# watchplb.net
KiCad netlist of a schematic drawn in EAGLE
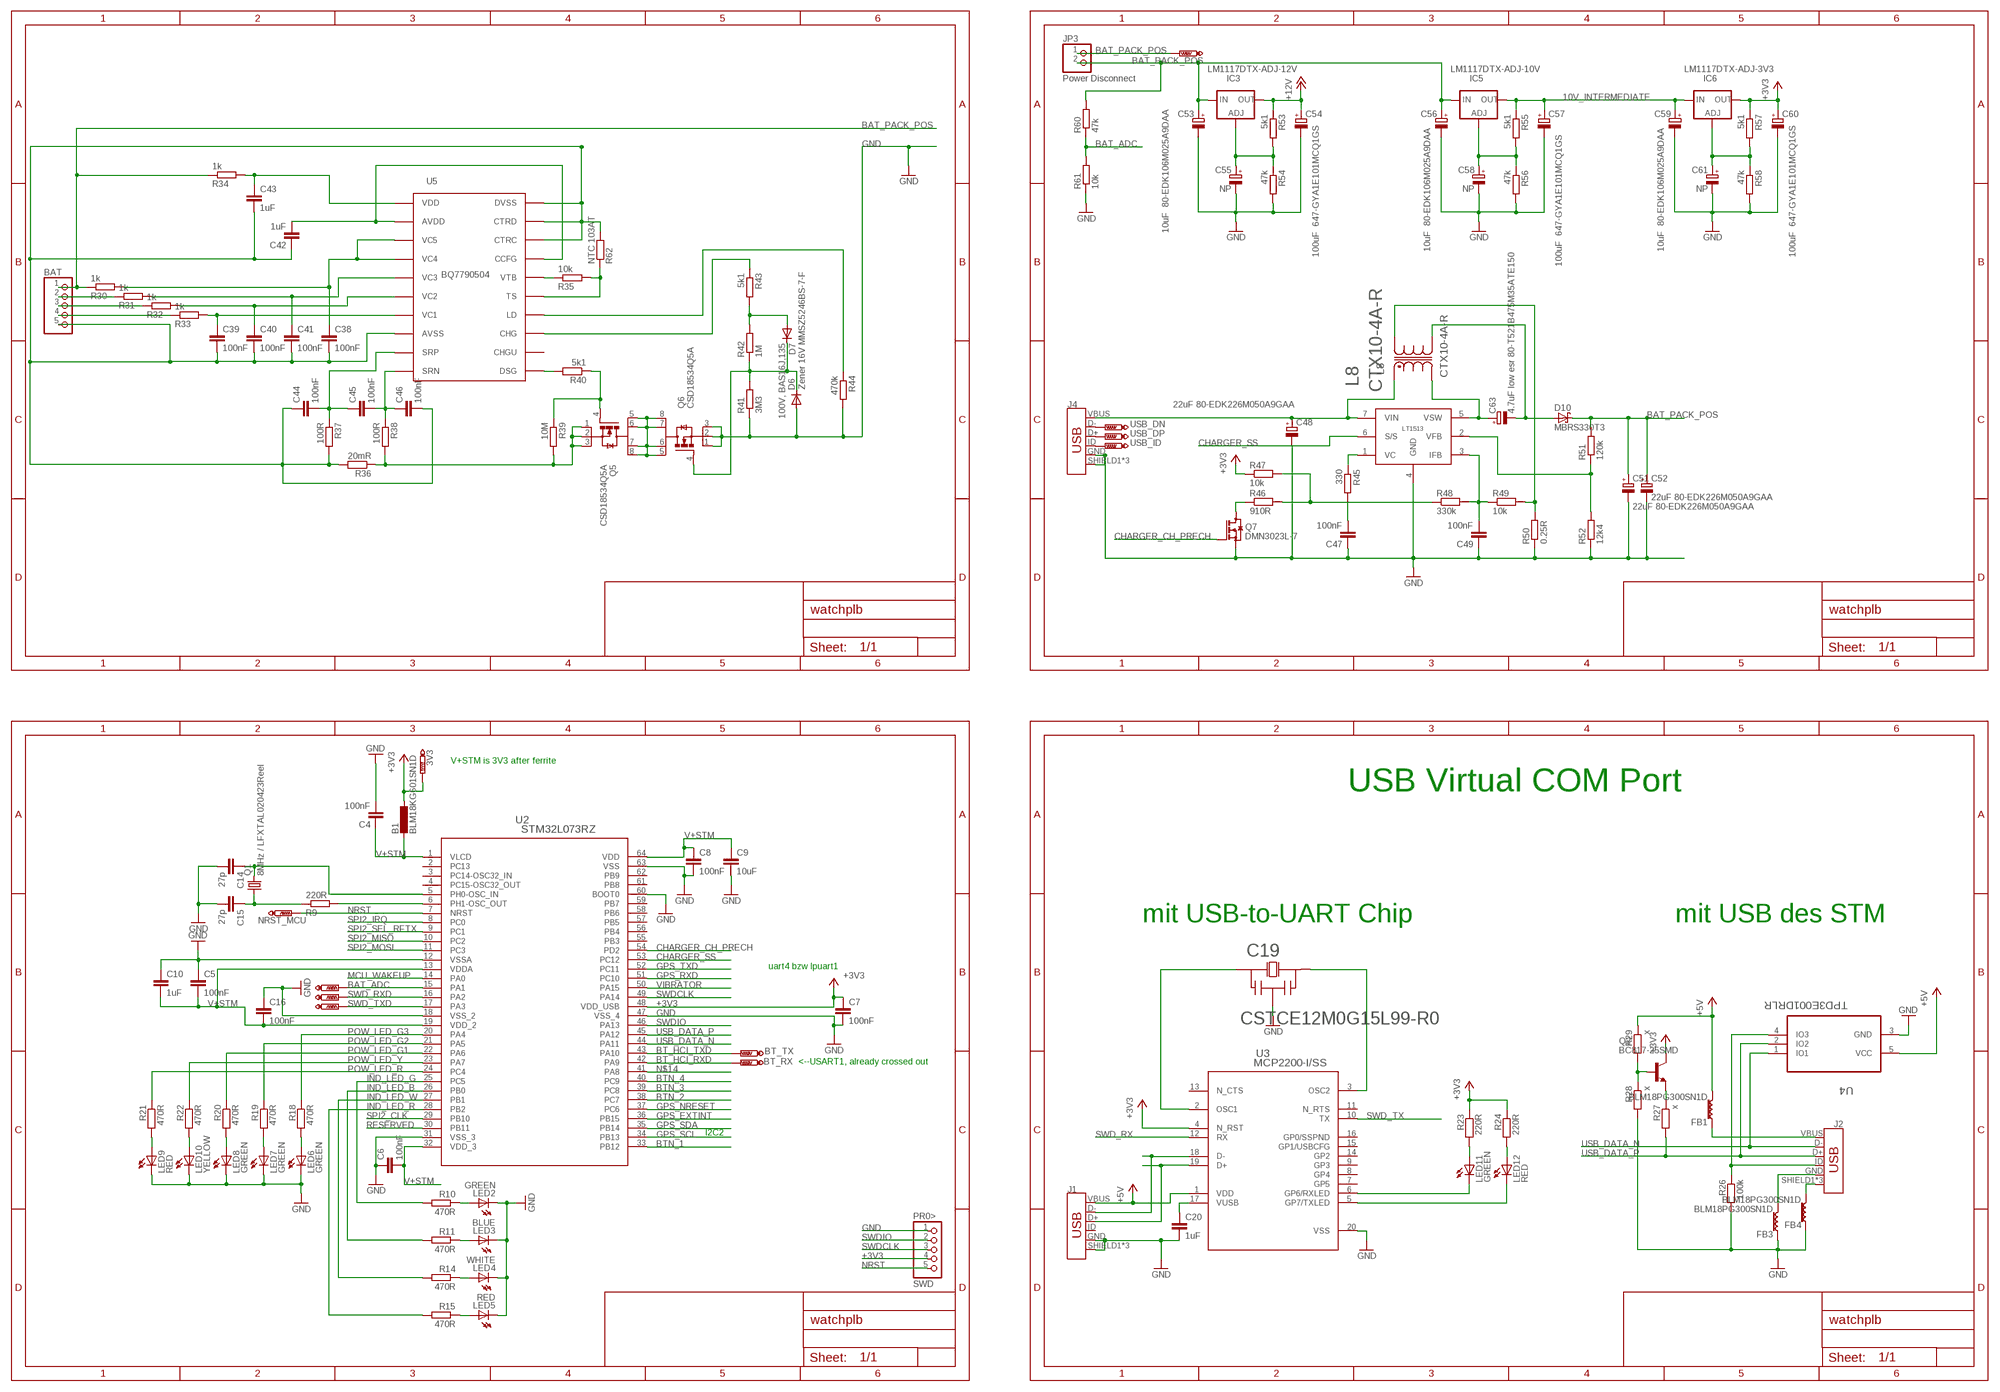
[diagram p0: schematic, sheet 1, part 1 of 2]
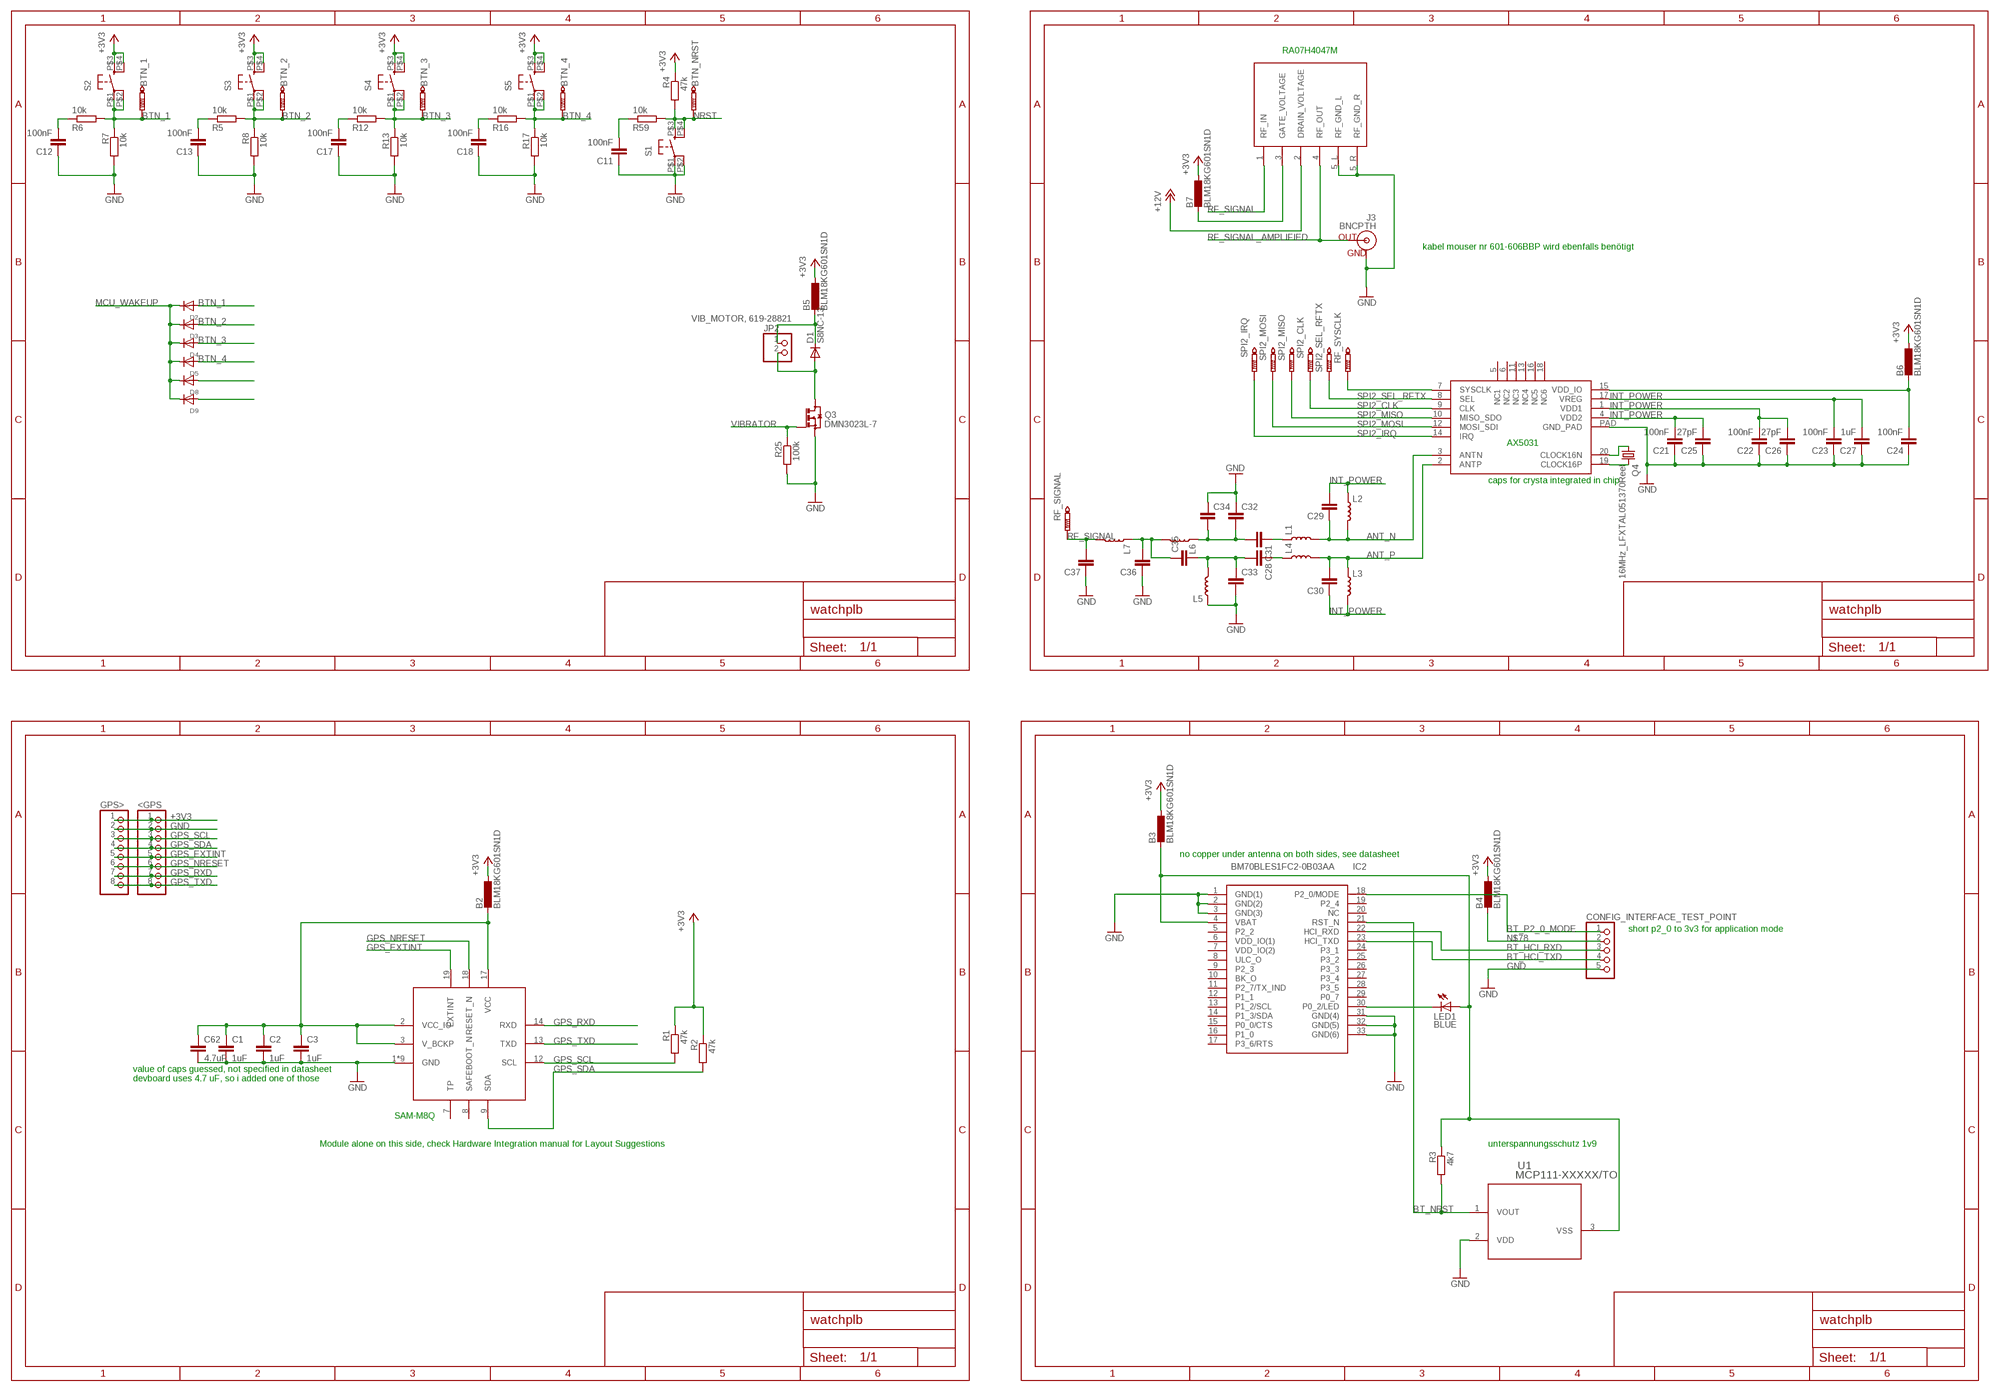
[diagram p1: schematic, sheet 1, part 2 of 2]

(export (version "E")
  (design (tool "Eeschema 10.0.6"))
  (components
    (comp (ref "3V3")
      (value "PTR1B2,54")
      (footprint "eagle-import:B2,54")
      (libsource (lib "eagle-import") (part "PTR1B2,54"))
    )
    (comp (ref "<GPS")
      (value "PINHD-1X8")
      (footprint "eagle-import:1X08")
      (libsource (lib "eagle-import") (part "PINHD-1X8"))
    )
    (comp (ref "B1")
      (value "BLM18KG601SN1D")
      (footprint "eagle-import:L0603")
      (libsource (lib "eagle-import") (part "B-EU_B0603"))
    )
    (comp (ref "B2")
      (value "BLM18KG601SN1D")
      (footprint "eagle-import:L0603")
      (libsource (lib "eagle-import") (part "B-EU_B0603"))
    )
    (comp (ref "B3")
      (value "BLM18KG601SN1D")
      (footprint "eagle-import:L0603")
      (libsource (lib "eagle-import") (part "B-EU_B0603"))
    )
    (comp (ref "B4")
      (value "BLM18KG601SN1D")
      (footprint "eagle-import:L0603")
      (libsource (lib "eagle-import") (part "B-EU_B0603"))
    )
    (comp (ref "B5")
      (value "BLM18KG601SN1D")
      (footprint "eagle-import:L0603")
      (libsource (lib "eagle-import") (part "B-EU_B0603"))
    )
    (comp (ref "B6")
      (value "BLM18KG601SN1D")
      (footprint "eagle-import:L0603")
      (libsource (lib "eagle-import") (part "B-EU_B0603"))
    )
    (comp (ref "B7")
      (value "BLM18KG601SN1D")
      (footprint "eagle-import:L0603")
      (libsource (lib "eagle-import") (part "B-EU_B0603"))
    )
    (comp (ref "BAT")
      (value "PINHD-1X5")
      (footprint "eagle-import:1X05")
      (libsource (lib "eagle-import") (part "PINHD-1X5"))
    )
    (comp (ref "BAT_ADC")
      (value "PTR1B2,54")
      (footprint "eagle-import:B2,54")
      (libsource (lib "eagle-import") (part "PTR1B2,54"))
    )
    (comp (ref "BAT_PACK_POS")
      (value "PTR1B2,54")
      (footprint "eagle-import:B2,54")
      (libsource (lib "eagle-import") (part "PTR1B2,54"))
    )
    (comp (ref "BTN_1")
      (value "PTR1B2,54")
      (footprint "eagle-import:B2,54")
      (libsource (lib "eagle-import") (part "PTR1B2,54"))
    )
    (comp (ref "BTN_2")
      (value "PTR1B2,54")
      (footprint "eagle-import:B2,54")
      (libsource (lib "eagle-import") (part "PTR1B2,54"))
    )
    (comp (ref "BTN_3")
      (value "PTR1B2,54")
      (footprint "eagle-import:B2,54")
      (libsource (lib "eagle-import") (part "PTR1B2,54"))
    )
    (comp (ref "BTN_4")
      (value "PTR1B2,54")
      (footprint "eagle-import:B2,54")
      (libsource (lib "eagle-import") (part "PTR1B2,54"))
    )
    (comp (ref "BTN_NRST")
      (value "PTR1B2,54")
      (footprint "eagle-import:B2,54")
      (libsource (lib "eagle-import") (part "PTR1B2,54"))
    )
    (comp (ref "BT_RX")
      (value "PTR1B2,54")
      (footprint "eagle-import:B2,54")
      (libsource (lib "eagle-import") (part "PTR1B2,54"))
    )
    (comp (ref "BT_TX")
      (value "PTR1B2,54")
      (footprint "eagle-import:B2,54")
      (libsource (lib "eagle-import") (part "PTR1B2,54"))
    )
    (comp (ref "C1")
      (value "1uF")
      (footprint "eagle-import:C0805")
      (libsource (lib "eagle-import") (part "C-EUC0805"))
    )
    (comp (ref "C2")
      (value "1uF")
      (footprint "eagle-import:C0805")
      (libsource (lib "eagle-import") (part "C-EUC0805"))
    )
    (comp (ref "C3")
      (value "1uF")
      (footprint "eagle-import:C0805")
      (libsource (lib "eagle-import") (part "C-EUC0805"))
    )
    (comp (ref "C4")
      (value "100nF")
      (footprint "eagle-import:C0805")
      (libsource (lib "eagle-import") (part "C-EUC0805"))
    )
    (comp (ref "C5")
      (value "100nF")
      (footprint "eagle-import:C0805")
      (libsource (lib "eagle-import") (part "C-EUC0805"))
    )
    (comp (ref "C6")
      (value "100nF")
      (footprint "eagle-import:C0805")
      (libsource (lib "eagle-import") (part "C-EUC0805"))
    )
    (comp (ref "C7")
      (value "100nF")
      (footprint "eagle-import:C0805")
      (libsource (lib "eagle-import") (part "C-EUC0805"))
    )
    (comp (ref "C8")
      (value "100nF")
      (footprint "eagle-import:C0805")
      (libsource (lib "eagle-import") (part "C-EUC0805"))
    )
    (comp (ref "C9")
      (value "10uF")
      (footprint "eagle-import:C1206")
      (libsource (lib "eagle-import") (part "C-EUC1206"))
    )
    (comp (ref "C10")
      (value "1uF")
      (footprint "eagle-import:C0805")
      (libsource (lib "eagle-import") (part "C-EUC0805"))
    )
    (comp (ref "C11")
      (value "100nF")
      (footprint "eagle-import:C0805")
      (libsource (lib "eagle-import") (part "C-EUC0805"))
    )
    (comp (ref "C12")
      (value "100nF")
      (footprint "eagle-import:C0805")
      (libsource (lib "eagle-import") (part "C-EUC0805"))
    )
    (comp (ref "C13")
      (value "100nF")
      (footprint "eagle-import:C0805")
      (libsource (lib "eagle-import") (part "C-EUC0805"))
    )
    (comp (ref "C14")
      (value "27p")
      (footprint "eagle-import:C0805")
      (libsource (lib "eagle-import") (part "C-EUC0805"))
    )
    (comp (ref "C15")
      (value "27p")
      (footprint "eagle-import:C0805")
      (libsource (lib "eagle-import") (part "C-EUC0805"))
    )
    (comp (ref "C16")
      (value "100nF")
      (footprint "eagle-import:C0805")
      (libsource (lib "eagle-import") (part "C-EUC0805"))
    )
    (comp (ref "C17")
      (value "100nF")
      (footprint "eagle-import:C0805")
      (libsource (lib "eagle-import") (part "C-EUC0805"))
    )
    (comp (ref "C18")
      (value "100nF")
      (footprint "eagle-import:C0805")
      (libsource (lib "eagle-import") (part "C-EUC0805"))
    )
    (comp (ref "C19")
      (value "CSTCE12M0G15L99-R0")
      (footprint "eagle-import:CSTCE")
      (fields (field (name "MANUFACTURER_PART_NUMBER") "CSTCE8M00G52R0"))
      (libsource (lib "eagle-import") (part "CSTCE8M00G52-R0"))
    )
    (comp (ref "C20")
      (value "1uF")
      (footprint "eagle-import:C0805")
      (libsource (lib "eagle-import") (part "C-EUC0805"))
    )
    (comp (ref "C21")
      (value "100nF")
      (footprint "eagle-import:C0805")
      (libsource (lib "eagle-import") (part "C-EUC0805"))
    )
    (comp (ref "C22")
      (value "100nF")
      (footprint "eagle-import:C0805")
      (libsource (lib "eagle-import") (part "C-EUC0805"))
    )
    (comp (ref "C23")
      (value "100nF")
      (footprint "eagle-import:C0805")
      (libsource (lib "eagle-import") (part "C-EUC0805"))
    )
    (comp (ref "C24")
      (value "100nF")
      (footprint "eagle-import:C0805")
      (libsource (lib "eagle-import") (part "C-EUC0805"))
    )
    (comp (ref "C25")
      (value "27pF")
      (footprint "eagle-import:C0805")
      (libsource (lib "eagle-import") (part "C-EUC0805"))
    )
    (comp (ref "C26")
      (value "27pF")
      (footprint "eagle-import:C0805")
      (libsource (lib "eagle-import") (part "C-EUC0805"))
    )
    (comp (ref "C27")
      (value "1uF")
      (footprint "eagle-import:C0805")
      (libsource (lib "eagle-import") (part "C-EUC0805"))
    )
    (comp (ref "C28")
      (value "C-EUC0805")
      (footprint "eagle-import:C0805")
      (libsource (lib "eagle-import") (part "C-EUC0805"))
    )
    (comp (ref "C29")
      (value "C-EUC0805")
      (footprint "eagle-import:C0805")
      (libsource (lib "eagle-import") (part "C-EUC0805"))
    )
    (comp (ref "C30")
      (value "C-EUC0805")
      (footprint "eagle-import:C0805")
      (libsource (lib "eagle-import") (part "C-EUC0805"))
    )
    (comp (ref "C31")
      (value "C-EUC0805")
      (footprint "eagle-import:C0805")
      (libsource (lib "eagle-import") (part "C-EUC0805"))
    )
    (comp (ref "C32")
      (value "C-EUC0805")
      (footprint "eagle-import:C0805")
      (libsource (lib "eagle-import") (part "C-EUC0805"))
    )
    (comp (ref "C33")
      (value "C-EUC0805")
      (footprint "eagle-import:C0805")
      (libsource (lib "eagle-import") (part "C-EUC0805"))
    )
    (comp (ref "C34")
      (value "C-EUC0805")
      (footprint "eagle-import:C0805")
      (libsource (lib "eagle-import") (part "C-EUC0805"))
    )
    (comp (ref "C35")
      (value "C-EUC0805")
      (footprint "eagle-import:C0805")
      (libsource (lib "eagle-import") (part "C-EUC0805"))
    )
    (comp (ref "C36")
      (value "C-EUC0805")
      (footprint "eagle-import:C0805")
      (libsource (lib "eagle-import") (part "C-EUC0805"))
    )
    (comp (ref "C37")
      (value "C-EUC0805")
      (footprint "eagle-import:C0805")
      (libsource (lib "eagle-import") (part "C-EUC0805"))
    )
    (comp (ref "C38")
      (value "100nF")
      (footprint "eagle-import:C0805K")
      (libsource (lib "eagle-import") (part "C-EUC0805K"))
    )
    (comp (ref "C39")
      (value "100nF")
      (footprint "eagle-import:C0805K")
      (libsource (lib "eagle-import") (part "C-EUC0805K"))
    )
    (comp (ref "C40")
      (value "100nF")
      (footprint "eagle-import:C0805K")
      (libsource (lib "eagle-import") (part "C-EUC0805K"))
    )
    (comp (ref "C41")
      (value "100nF")
      (footprint "eagle-import:C0805K")
      (libsource (lib "eagle-import") (part "C-EUC0805K"))
    )
    (comp (ref "C42")
      (value "1uF")
      (footprint "eagle-import:C0805K")
      (libsource (lib "eagle-import") (part "C-EUC0805K"))
    )
    (comp (ref "C43")
      (value "1uF")
      (footprint "eagle-import:C0805K")
      (libsource (lib "eagle-import") (part "C-EUC0805K"))
    )
    (comp (ref "C44")
      (value "100nF")
      (footprint "eagle-import:C0805K")
      (libsource (lib "eagle-import") (part "C-EUC0805K"))
    )
    (comp (ref "C45")
      (value "100nF")
      (footprint "eagle-import:C0805K")
      (libsource (lib "eagle-import") (part "C-EUC0805K"))
    )
    (comp (ref "C46")
      (value "100nF")
      (footprint "eagle-import:C0805K")
      (libsource (lib "eagle-import") (part "C-EUC0805K"))
    )
    (comp (ref "C47")
      (value "100nF")
      (footprint "eagle-import:C0805K")
      (libsource (lib "eagle-import") (part "C-EUC0805K"))
    )
    (comp (ref "C48")
      (value "22uF 80-EDK226M050A9GAA")
      (footprint "eagle-import:PANASONIC_E")
      (libsource (lib "eagle-import") (part "CPOL-EUE"))
    )
    (comp (ref "C49")
      (value "100nF")
      (footprint "eagle-import:C0805K")
      (libsource (lib "eagle-import") (part "C-EUC0805K"))
    )
    (comp (ref "C51")
      (value "22uF 80-EDK226M050A9GAA")
      (footprint "eagle-import:PANASONIC_E")
      (libsource (lib "eagle-import") (part "CPOL-EUE"))
    )
    (comp (ref "C52")
      (value "22uF 80-EDK226M050A9GAA")
      (footprint "eagle-import:PANASONIC_E")
      (libsource (lib "eagle-import") (part "CPOL-EUE"))
    )
    (comp (ref "C53")
      (value "10uF 80-EDK106M025A9DAA")
      (footprint "eagle-import:PANASONIC_E")
      (libsource (lib "eagle-import") (part "CPOL-EUE"))
    )
    (comp (ref "C54")
      (value "100uF 647-GYA1E101MCQ1GS")
      (footprint "eagle-import:PANASONIC_E")
      (libsource (lib "eagle-import") (part "CPOL-EUE"))
    )
    (comp (ref "C55")
      (value "NP")
      (footprint "eagle-import:PANASONIC_E")
      (libsource (lib "eagle-import") (part "CPOL-EUE"))
    )
    (comp (ref "C56")
      (value "10uF 80-EDK106M025A9DAA")
      (footprint "eagle-import:PANASONIC_E")
      (libsource (lib "eagle-import") (part "CPOL-EUE"))
    )
    (comp (ref "C57")
      (value "100uF 647-GYA1E101MCQ1GS")
      (footprint "eagle-import:PANASONIC_E")
      (libsource (lib "eagle-import") (part "CPOL-EUE"))
    )
    (comp (ref "C58")
      (value "NP")
      (footprint "eagle-import:PANASONIC_E")
      (libsource (lib "eagle-import") (part "CPOL-EUE"))
    )
    (comp (ref "C59")
      (value "10uF 80-EDK106M025A9DAA")
      (footprint "eagle-import:PANASONIC_E")
      (libsource (lib "eagle-import") (part "CPOL-EUE"))
    )
    (comp (ref "C60")
      (value "100uF 647-GYA1E101MCQ1GS")
      (footprint "eagle-import:PANASONIC_E")
      (libsource (lib "eagle-import") (part "CPOL-EUE"))
    )
    (comp (ref "C61")
      (value "NP")
      (footprint "eagle-import:PANASONIC_E")
      (libsource (lib "eagle-import") (part "CPOL-EUE"))
    )
    (comp (ref "C62")
      (value "4.7uF")
      (footprint "eagle-import:C0805")
      (libsource (lib "eagle-import") (part "C-EUC0805"))
    )
    (comp (ref "C63")
      (value "4.7uF low esr 80-T521B475M35ATE150")
      (footprint "eagle-import:B_3528-21R")
      (libsource (lib "eagle-import") (part "CPOL-EUB/3528-21R"))
    )
    (comp (ref "CONFIG_INTERFACE_TEST_POINT")
      (value "PINHD-1X5")
      (footprint "eagle-import:1X05")
      (libsource (lib "eagle-import") (part "PINHD-1X5"))
    )
    (comp (ref "D1")
      (value "S8NC-13")
      (footprint "eagle-import:SMC")
      (libsource (lib "eagle-import") (part "DIODE-SMC"))
    )
    (comp (ref "D2")
      (value "DIODESOD-123")
      (footprint "eagle-import:SOD-123")
      (libsource (lib "eagle-import") (part "DIODESOD-123"))
    )
    (comp (ref "D3")
      (value "DIODESOD-123")
      (footprint "eagle-import:SOD-123")
      (libsource (lib "eagle-import") (part "DIODESOD-123"))
    )
    (comp (ref "D4")
      (value "DIODESOD-123")
      (footprint "eagle-import:SOD-123")
      (libsource (lib "eagle-import") (part "DIODESOD-123"))
    )
    (comp (ref "D5")
      (value "DIODESOD-123")
      (footprint "eagle-import:SOD-123")
      (libsource (lib "eagle-import") (part "DIODESOD-123"))
    )
    (comp (ref "D6")
      (value "Zener 16V MMSZ5246BS-7-F")
      (footprint "eagle-import:SOD323-R")
      (libsource (lib "eagle-import") (part "diode-1_DIODE-SOD323-R"))
    )
    (comp (ref "D7")
      (value "100V, BAS16J,135")
      (footprint "eagle-import:SOD323-R")
      (libsource (lib "eagle-import") (part "diode-1_DIODE-SOD323-R"))
    )
    (comp (ref "D8")
      (value "DIODESOD-123")
      (footprint "eagle-import:SOD-123")
      (libsource (lib "eagle-import") (part "DIODESOD-123"))
    )
    (comp (ref "D9")
      (value "DIODESOD-123")
      (footprint "eagle-import:SOD-123")
      (libsource (lib "eagle-import") (part "DIODESOD-123"))
    )
    (comp (ref "D10")
      (value "MBRS330T3")
      (footprint "eagle-import:SMC")
      (libsource (lib "eagle-import") (part "MBRS30T33"))
    )
    (comp (ref "FB1")
      (value "BLM18PG300SN1D")
      (footprint "eagle-import:0603")
      (libsource (lib "eagle-import") (part "FERRITE_BEAD-0603"))
    )
    (comp (ref "FB3")
      (value "BLM18PG300SN1D")
      (footprint "eagle-import:0603")
      (libsource (lib "eagle-import") (part "FERRITE_BEAD-0603"))
    )
    (comp (ref "FB4")
      (value "BLM18PG300SN1D")
      (footprint "eagle-import:0603")
      (libsource (lib "eagle-import") (part "FERRITE_BEAD-0603"))
    )
    (comp (ref "GPS>")
      (value "PINHD-1X8")
      (footprint "eagle-import:1X08")
      (libsource (lib "eagle-import") (part "PINHD-1X8"))
    )
    (comp (ref "IC1")
      (value "SAM-M8Q")
      (footprint "eagle-import:SAM-M8Q")
      (libsource (lib "eagle-import") (part "SAM-M8Q"))
    )
    (comp (ref "IC2")
      (value "BM70BLES1FC2-0B03AA")
      (footprint "eagle-import:BM78SPPS5NC2_1")
      (libsource (lib "eagle-import") (part "BM70BLES1FC2-0B03AA"))
    )
    (comp (ref "IC3")
      (value "LM1117DTX-ADJ-12V")
      (footprint "eagle-import:TO252")
      (libsource (lib "eagle-import") (part "LM1117DTX-ADJ"))
    )
    (comp (ref "IC5")
      (value "LM1117DTX-ADJ-10V")
      (footprint "eagle-import:TO252")
      (libsource (lib "eagle-import") (part "LM1117DTX-ADJ"))
    )
    (comp (ref "IC6")
      (value "LM1117DTX-ADJ-3V3")
      (footprint "eagle-import:TO252")
      (libsource (lib "eagle-import") (part "LM1117DTX-ADJ"))
    )
    (comp (ref "J1")
      (value "USB_MICRO-B_FEMALE-SMT")
      (footprint "eagle-import:USB-B-MICRO-SMD")
      (libsource (lib "eagle-import") (part "USB_MICRO-B_FEMALE-SMT"))
    )
    (comp (ref "J2")
      (value "USB_MICRO-B_FEMALE-SMT")
      (footprint "eagle-import:USB-B-MICRO-SMD")
      (libsource (lib "eagle-import") (part "USB_MICRO-B_FEMALE-SMT"))
    )
    (comp (ref "J3")
      (value "BNCPTH")
      (footprint "eagle-import:BNC")
      (libsource (lib "eagle-import") (part "BNCPTH"))
    )
    (comp (ref "J4")
      (value "USB_MICRO-B_FEMALE-SMT")
      (footprint "eagle-import:USB-B-MICRO-SMD")
      (libsource (lib "eagle-import") (part "USB_MICRO-B_FEMALE-SMT"))
    )
    (comp (ref "JP2")
      (value "VIB_MOTOR, 619-28821")
      (footprint "eagle-import:1X02")
      (libsource (lib "eagle-import") (part "PINHD-1X2"))
    )
    (comp (ref "JP3")
      (value "Power Disconnect")
      (footprint "eagle-import:1X02")
      (libsource (lib "eagle-import") (part "PINHD-1X2"))
    )
    (comp (ref "L1")
      (value "INDUCTOR-0805-3.3UH")
      (footprint "eagle-import:0805")
      (libsource (lib "eagle-import") (part "INDUCTOR-0805-3.3UH"))
    )
    (comp (ref "L2")
      (value "INDUCTOR-0805-3.3UH")
      (footprint "eagle-import:0805")
      (libsource (lib "eagle-import") (part "INDUCTOR-0805-3.3UH"))
    )
    (comp (ref "L3")
      (value "INDUCTOR-0805-3.3UH")
      (footprint "eagle-import:0805")
      (libsource (lib "eagle-import") (part "INDUCTOR-0805-3.3UH"))
    )
    (comp (ref "L4")
      (value "INDUCTOR-0805-3.3UH")
      (footprint "eagle-import:0805")
      (libsource (lib "eagle-import") (part "INDUCTOR-0805-3.3UH"))
    )
    (comp (ref "L5")
      (value "INDUCTOR-0805-3.3UH")
      (footprint "eagle-import:0805")
      (libsource (lib "eagle-import") (part "INDUCTOR-0805-3.3UH"))
    )
    (comp (ref "L6")
      (value "INDUCTOR-0805-3.3UH")
      (footprint "eagle-import:0805")
      (libsource (lib "eagle-import") (part "INDUCTOR-0805-3.3UH"))
    )
    (comp (ref "L7")
      (value "INDUCTOR-0805-3.3UH")
      (footprint "eagle-import:0805")
      (libsource (lib "eagle-import") (part "INDUCTOR-0805-3.3UH"))
    )
    (comp (ref "L8")
      (value "CTX10-4A-R")
      (footprint "eagle-import:INDM115115X635N")
      (fields (field (name "MF") "Eaton"))
      (libsource (lib "eagle-import") (part "CTX10-4A-R"))
    )
    (comp (ref "LED1")
      (value "BLUE")
      (footprint "eagle-import:CHIP-LED0805")
      (libsource (lib "eagle-import") (part "LEDCHIP-LED0805"))
    )
    (comp (ref "LED2")
      (value "GREEN")
      (footprint "eagle-import:CHIP-LED0805")
      (libsource (lib "eagle-import") (part "LEDCHIP-LED0805"))
    )
    (comp (ref "LED3")
      (value "BLUE")
      (footprint "eagle-import:CHIP-LED0805")
      (libsource (lib "eagle-import") (part "LEDCHIP-LED0805"))
    )
    (comp (ref "LED4")
      (value "WHITE")
      (footprint "eagle-import:CHIP-LED0805")
      (libsource (lib "eagle-import") (part "LEDCHIP-LED0805"))
    )
    (comp (ref "LED5")
      (value "RED")
      (footprint "eagle-import:CHIP-LED0805")
      (libsource (lib "eagle-import") (part "LEDCHIP-LED0805"))
    )
    (comp (ref "LED6")
      (value "GREEN")
      (footprint "eagle-import:CHIP-LED0805")
      (libsource (lib "eagle-import") (part "LEDCHIP-LED0805"))
    )
    (comp (ref "LED7")
      (value "GREEN")
      (footprint "eagle-import:CHIP-LED0805")
      (libsource (lib "eagle-import") (part "LEDCHIP-LED0805"))
    )
    (comp (ref "LED8")
      (value "GREEN")
      (footprint "eagle-import:CHIP-LED0805")
      (libsource (lib "eagle-import") (part "LEDCHIP-LED0805"))
    )
    (comp (ref "LED9")
      (value "RED")
      (footprint "eagle-import:CHIP-LED0805")
      (libsource (lib "eagle-import") (part "LEDCHIP-LED0805"))
    )
    (comp (ref "LED10")
      (value "YELLOW")
      (footprint "eagle-import:CHIP-LED0805")
      (libsource (lib "eagle-import") (part "LEDCHIP-LED0805"))
    )
    (comp (ref "LED11")
      (value "GREEN")
      (footprint "eagle-import:CHIP-LED0805")
      (libsource (lib "eagle-import") (part "LEDCHIP-LED0805"))
    )
    (comp (ref "LED12")
      (value "RED")
      (footprint "eagle-import:CHIP-LED0805")
      (libsource (lib "eagle-import") (part "LEDCHIP-LED0805"))
    )
    (comp (ref "NRST_MCU")
      (value "PTR1B2,54")
      (footprint "eagle-import:B2,54")
      (libsource (lib "eagle-import") (part "PTR1B2,54"))
    )
    (comp (ref "PR0>")
      (value "SWD")
      (footprint "eagle-import:1X05")
      (libsource (lib "eagle-import") (part "PINHD-1X5"))
    )
    (comp (ref "Q1")
      (value "8MHz / LFXTAL020423Reel")
      (footprint "eagle-import:HC49UP")
      (libsource (lib "eagle-import") (part "crystal_CRYSTALHC49UP"))
    )
    (comp (ref "Q2")
      (value "BC817-25SMD")
      (footprint "eagle-import:SOT23-BEC")
      (libsource (lib "eagle-import") (part "BC817SMD-25"))
    )
    (comp (ref "Q3")
      (value "DMN3023L-7")
      (footprint "eagle-import:SOT23")
      (libsource (lib "eagle-import") (part "BSS123"))
    )
    (comp (ref "Q4")
      (value "16MHz_LFXTAL051370Reel")
      (footprint "eagle-import:HC49UP")
      (libsource (lib "eagle-import") (part "CRYSTALHC49UP"))
    )
    (comp (ref "Q5")
      (value "CSD18534Q5A")
      (footprint "eagle-import:TRANS_CSD18534Q5A")
      (fields (field (name "MF") "Texas Instruments"))
      (libsource (lib "eagle-import") (part "CSD18534Q5A"))
    )
    (comp (ref "Q6")
      (value "CSD18534Q5A")
      (footprint "eagle-import:TRANS_CSD18534Q5A")
      (fields (field (name "MF") "Texas Instruments"))
      (libsource (lib "eagle-import") (part "CSD18534Q5A"))
    )
    (comp (ref "Q7")
      (value "DMN3023L-7")
      (footprint "eagle-import:SOT23")
      (libsource (lib "eagle-import") (part "BSS123"))
    )
    (comp (ref "R1")
      (value "47k")
      (footprint "eagle-import:M0805")
      (libsource (lib "eagle-import") (part "R-EU_M0805"))
    )
    (comp (ref "R2")
      (value "47k")
      (footprint "eagle-import:M0805")
      (libsource (lib "eagle-import") (part "R-EU_M0805"))
    )
    (comp (ref "R3")
      (value "4k7")
      (footprint "eagle-import:M0805")
      (libsource (lib "eagle-import") (part "R-EU_M0805"))
    )
    (comp (ref "R4")
      (value "47k")
      (footprint "eagle-import:M0805")
      (libsource (lib "eagle-import") (part "R-EU_M0805"))
    )
    (comp (ref "R5")
      (value "10k")
      (footprint "eagle-import:M0805")
      (libsource (lib "eagle-import") (part "R-EU_M0805"))
    )
    (comp (ref "R6")
      (value "10k")
      (footprint "eagle-import:M0805")
      (libsource (lib "eagle-import") (part "R-EU_M0805"))
    )
    (comp (ref "R7")
      (value "10k")
      (footprint "eagle-import:M0805")
      (libsource (lib "eagle-import") (part "R-EU_M0805"))
    )
    (comp (ref "R8")
      (value "10k")
      (footprint "eagle-import:M0805")
      (libsource (lib "eagle-import") (part "R-EU_M0805"))
    )
    (comp (ref "R9")
      (value "220R")
      (footprint "eagle-import:M0805")
      (libsource (lib "eagle-import") (part "R-EU_M0805"))
    )
    (comp (ref "R10")
      (value "470R")
      (footprint "eagle-import:M0805")
      (libsource (lib "eagle-import") (part "R-EU_M0805"))
    )
    (comp (ref "R11")
      (value "470R")
      (footprint "eagle-import:M0805")
      (libsource (lib "eagle-import") (part "R-EU_M0805"))
    )
    (comp (ref "R12")
      (value "10k")
      (footprint "eagle-import:M0805")
      (libsource (lib "eagle-import") (part "R-EU_M0805"))
    )
    (comp (ref "R13")
      (value "10k")
      (footprint "eagle-import:M0805")
      (libsource (lib "eagle-import") (part "R-EU_M0805"))
    )
    (comp (ref "R14")
      (value "470R")
      (footprint "eagle-import:M0805")
      (libsource (lib "eagle-import") (part "R-EU_M0805"))
    )
    (comp (ref "R15")
      (value "470R")
      (footprint "eagle-import:M0805")
      (libsource (lib "eagle-import") (part "R-EU_M0805"))
    )
    (comp (ref "R16")
      (value "10k")
      (footprint "eagle-import:M0805")
      (libsource (lib "eagle-import") (part "R-EU_M0805"))
    )
    (comp (ref "R17")
      (value "10k")
      (footprint "eagle-import:M0805")
      (libsource (lib "eagle-import") (part "R-EU_M0805"))
    )
    (comp (ref "R18")
      (value "470R")
      (footprint "eagle-import:M0805")
      (libsource (lib "eagle-import") (part "R-EU_M0805"))
    )
    (comp (ref "R19")
      (value "470R")
      (footprint "eagle-import:M0805")
      (libsource (lib "eagle-import") (part "R-EU_M0805"))
    )
    (comp (ref "R20")
      (value "470R")
      (footprint "eagle-import:M0805")
      (libsource (lib "eagle-import") (part "R-EU_M0805"))
    )
    (comp (ref "R21")
      (value "470R")
      (footprint "eagle-import:M0805")
      (libsource (lib "eagle-import") (part "R-EU_M0805"))
    )
    (comp (ref "R22")
      (value "470R")
      (footprint "eagle-import:M0805")
      (libsource (lib "eagle-import") (part "R-EU_M0805"))
    )
    (comp (ref "R23")
      (value "220R")
      (footprint "eagle-import:M0805")
      (libsource (lib "eagle-import") (part "R-EU_M0805"))
    )
    (comp (ref "R24")
      (value "220R")
      (footprint "eagle-import:M0805")
      (libsource (lib "eagle-import") (part "R-EU_M0805"))
    )
    (comp (ref "R25")
      (value "100k")
      (footprint "eagle-import:M0805")
      (libsource (lib "eagle-import") (part "R-EU_M0805"))
    )
    (comp (ref "R26")
      (value "100k")
      (footprint "eagle-import:M0805")
      (libsource (lib "eagle-import") (part "R-EU_M0805"))
    )
    (comp (ref "R27")
      (value "x")
      (footprint "eagle-import:M0805")
      (libsource (lib "eagle-import") (part "R-EU_M0805"))
    )
    (comp (ref "R28")
      (value "x")
      (footprint "eagle-import:M0805")
      (libsource (lib "eagle-import") (part "R-EU_M0805"))
    )
    (comp (ref "R29")
      (value "x")
      (footprint "eagle-import:M0805")
      (libsource (lib "eagle-import") (part "R-EU_M0805"))
    )
    (comp (ref "R30")
      (value "1k")
      (footprint "eagle-import:M0805")
      (libsource (lib "eagle-import") (part "R-EU_M0805"))
    )
    (comp (ref "R31")
      (value "1k")
      (footprint "eagle-import:M0805")
      (libsource (lib "eagle-import") (part "R-EU_M0805"))
    )
    (comp (ref "R32")
      (value "1k")
      (footprint "eagle-import:M0805")
      (libsource (lib "eagle-import") (part "R-EU_M0805"))
    )
    (comp (ref "R33")
      (value "1k")
      (footprint "eagle-import:M0805")
      (libsource (lib "eagle-import") (part "R-EU_M0805"))
    )
    (comp (ref "R34")
      (value "1k")
      (footprint "eagle-import:M0805")
      (libsource (lib "eagle-import") (part "R-EU_M0805"))
    )
    (comp (ref "R35")
      (value "10k")
      (footprint "eagle-import:M0805")
      (libsource (lib "eagle-import") (part "R-EU_M0805"))
    )
    (comp (ref "R36")
      (value "20mR")
      (footprint "eagle-import:R2512")
      (libsource (lib "eagle-import") (part "R-EU_R2512"))
    )
    (comp (ref "R37")
      (value "100R")
      (footprint "eagle-import:M0805")
      (libsource (lib "eagle-import") (part "R-EU_M0805"))
    )
    (comp (ref "R38")
      (value "100R")
      (footprint "eagle-import:M0805")
      (libsource (lib "eagle-import") (part "R-EU_M0805"))
    )
    (comp (ref "R39")
      (value "10M")
      (footprint "eagle-import:M0805")
      (libsource (lib "eagle-import") (part "R-EU_M0805"))
    )
    (comp (ref "R40")
      (value "5k1")
      (footprint "eagle-import:M0805")
      (libsource (lib "eagle-import") (part "R-EU_M0805"))
    )
    (comp (ref "R41")
      (value "3M3")
      (footprint "eagle-import:M0805")
      (libsource (lib "eagle-import") (part "R-EU_M0805"))
    )
    (comp (ref "R42")
      (value "1M")
      (footprint "eagle-import:M0805")
      (libsource (lib "eagle-import") (part "R-EU_M0805"))
    )
    (comp (ref "R43")
      (value "5k1")
      (footprint "eagle-import:M0805")
      (libsource (lib "eagle-import") (part "R-EU_M0805"))
    )
    (comp (ref "R44")
      (value "470k")
      (footprint "eagle-import:M0805")
      (libsource (lib "eagle-import") (part "R-EU_M0805"))
    )
    (comp (ref "R45")
      (value "330")
      (footprint "eagle-import:M0805")
      (libsource (lib "eagle-import") (part "R-EU_M0805"))
    )
    (comp (ref "R46")
      (value "910R")
      (footprint "eagle-import:M0805")
      (libsource (lib "eagle-import") (part "R-EU_M0805"))
    )
    (comp (ref "R47")
      (value "10k")
      (footprint "eagle-import:M0805")
      (libsource (lib "eagle-import") (part "R-EU_M0805"))
    )
    (comp (ref "R48")
      (value "330k")
      (footprint "eagle-import:M0805")
      (libsource (lib "eagle-import") (part "R-EU_M0805"))
    )
    (comp (ref "R49")
      (value "10k")
      (footprint "eagle-import:M0805")
      (libsource (lib "eagle-import") (part "R-EU_M0805"))
    )
    (comp (ref "R50")
      (value "0.25R")
      (footprint "eagle-import:R2512")
      (libsource (lib "eagle-import") (part "R-EU_R2512"))
    )
    (comp (ref "R51")
      (value "120k")
      (footprint "eagle-import:M0805")
      (libsource (lib "eagle-import") (part "R-EU_M0805"))
    )
    (comp (ref "R52")
      (value "12k4")
      (footprint "eagle-import:M0805")
      (libsource (lib "eagle-import") (part "R-EU_M0805"))
    )
    (comp (ref "R53")
      (value "5k1")
      (footprint "eagle-import:M0805")
      (libsource (lib "eagle-import") (part "R-EU_M0805"))
    )
    (comp (ref "R54")
      (value "47k")
      (footprint "eagle-import:M0805")
      (libsource (lib "eagle-import") (part "R-EU_M0805"))
    )
    (comp (ref "R55")
      (value "5k1")
      (footprint "eagle-import:M0805")
      (libsource (lib "eagle-import") (part "R-EU_M0805"))
    )
    (comp (ref "R56")
      (value "47k")
      (footprint "eagle-import:M0805")
      (libsource (lib "eagle-import") (part "R-EU_M0805"))
    )
    (comp (ref "R57")
      (value "5k1")
      (footprint "eagle-import:M0805")
      (libsource (lib "eagle-import") (part "R-EU_M0805"))
    )
    (comp (ref "R58")
      (value "47k")
      (footprint "eagle-import:M0805")
      (libsource (lib "eagle-import") (part "R-EU_M0805"))
    )
    (comp (ref "R59")
      (value "10k")
      (footprint "eagle-import:M0805")
      (libsource (lib "eagle-import") (part "R-EU_M0805"))
    )
    (comp (ref "R60")
      (value "47k")
      (footprint "eagle-import:M0805")
      (libsource (lib "eagle-import") (part "R-EU_M0805"))
    )
    (comp (ref "R61")
      (value "10k")
      (footprint "eagle-import:M0805")
      (libsource (lib "eagle-import") (part "R-EU_M0805"))
    )
    (comp (ref "R62")
      (value "NTC 103AT")
      (footprint "eagle-import:M0805")
      (libsource (lib "eagle-import") (part "R-EU_M0805"))
    )
    (comp (ref "RF_SIGNAL")
      (value "PTR1B2,54")
      (footprint "eagle-import:B2,54")
      (libsource (lib "eagle-import") (part "PTR1B2,54"))
    )
    (comp (ref "RF_SYSCLK")
      (value "PTR1B2,54")
      (footprint "eagle-import:B2,54")
      (libsource (lib "eagle-import") (part "PTR1B2,54"))
    )
    (comp (ref "S1")
      (value "TL3305")
      (footprint "eagle-import:SMD_SWITCH")
      (libsource (lib "eagle-import") (part "TL3305"))
    )
    (comp (ref "S2")
      (value "TL3305")
      (footprint "eagle-import:SMD_SWITCH")
      (libsource (lib "eagle-import") (part "TL3305"))
    )
    (comp (ref "S3")
      (value "TL3305")
      (footprint "eagle-import:SMD_SWITCH")
      (libsource (lib "eagle-import") (part "TL3305"))
    )
    (comp (ref "S4")
      (value "TL3305")
      (footprint "eagle-import:SMD_SWITCH")
      (libsource (lib "eagle-import") (part "TL3305"))
    )
    (comp (ref "S5")
      (value "TL3305")
      (footprint "eagle-import:SMD_SWITCH")
      (libsource (lib "eagle-import") (part "TL3305"))
    )
    (comp (ref "SPI2_CLK")
      (value "PTR1B2,54")
      (footprint "eagle-import:B2,54")
      (libsource (lib "eagle-import") (part "PTR1B2,54"))
    )
    (comp (ref "SPI2_IRQ")
      (value "PTR1B2,54")
      (footprint "eagle-import:B2,54")
      (libsource (lib "eagle-import") (part "PTR1B2,54"))
    )
    (comp (ref "SPI2_MISO")
      (value "PTR1B2,54")
      (footprint "eagle-import:B2,54")
      (libsource (lib "eagle-import") (part "PTR1B2,54"))
    )
    (comp (ref "SPI2_MOSI")
      (value "PTR1B2,54")
      (footprint "eagle-import:B2,54")
      (libsource (lib "eagle-import") (part "PTR1B2,54"))
    )
    (comp (ref "SPI2_SEL_RFTX")
      (value "PTR1B2,54")
      (footprint "eagle-import:B2,54")
      (libsource (lib "eagle-import") (part "PTR1B2,54"))
    )
    (comp (ref "SWD_RXD")
      (value "PTR1B2,54")
      (footprint "eagle-import:B2,54")
      (libsource (lib "eagle-import") (part "PTR1B2,54"))
    )
    (comp (ref "SWD_TXD")
      (value "PTR1B2,54")
      (footprint "eagle-import:B2,54")
      (libsource (lib "eagle-import") (part "PTR1B2,54"))
    )
    (comp (ref "U$1")
      (value "AX5031")
      (footprint "eagle-import:QFN20")
      (libsource (lib "eagle-import") (part "AX5031"))
    )
    (comp (ref "U$2")
      (value "RA07H4047M")
      (footprint "eagle-import:RA07H4047M")
      (libsource (lib "eagle-import") (part "RA07H4047M"))
    )
    (comp (ref "U$3")
      (value "LT1513")
      (footprint "eagle-import:TO220-7")
      (libsource (lib "eagle-import") (part "LT1513"))
    )
    (comp (ref "U1")
      (value "MCP111-XXXXX/TO")
      (footprint "eagle-import:TO-92_MC")
      (fields (field (name "MANUFACTURER_PART_NUMBER") "MCP111XXXXXTO"))
      (libsource (lib "eagle-import") (part "MCP111-XXXXX/TO"))
    )
    (comp (ref "U2")
      (value "STM32L073RZ")
      (footprint "eagle-import:LQFP64-10X10MM")
      (fields (field (name "MANUFACTURER_PART_NUMBER") "stm32l0x3rl"))
      (libsource (lib "eagle-import") (part "STM32L0X3RL"))
    )
    (comp (ref "U3")
      (value "MCP2200-I/SS")
      (footprint "eagle-import:SSOP20_MC")
      (fields (field (name "MANUFACTURER_PART_NUMBER") "mcp2200iss"))
      (libsource (lib "eagle-import") (part "MCP2200-I/SS"))
    )
    (comp (ref "U4")
      (value "TPD3E001DRLR")
      (footprint "eagle-import:SOT50P160X60-5N")
      (libsource (lib "eagle-import") (part "TPD3E001DRLR"))
    )
    (comp (ref "U5")
      (value "BQ7790504")
      (footprint "eagle-import:TSSOP-20_6MM")
      (libsource (lib "eagle-import") (part "BQ77904"))
    )
    (comp (ref "USB_DN")
      (value "PTR1B2,54")
      (footprint "eagle-import:B2,54")
      (libsource (lib "eagle-import") (part "PTR1B2,54"))
    )
    (comp (ref "USB_DP")
      (value "PTR1B2,54")
      (footprint "eagle-import:B2,54")
      (libsource (lib "eagle-import") (part "PTR1B2,54"))
    )
    (comp (ref "USB_ID")
      (value "PTR1B2,54")
      (footprint "eagle-import:B2,54")
      (libsource (lib "eagle-import") (part "PTR1B2,54"))
    )
  )
  (nets
    (net (code "1") (name "+3V3") (class "Default")
      (node (ref "3V3") (pin "TP") (pinfunction "TP_TP") (pintype "input"))
      (node (ref "<GPS") (pin "1") (pinfunction "1_1") (pintype "passive"))
      (node (ref "B1") (pin "1") (pinfunction "1_1") (pintype "passive"))
      (node (ref "B2") (pin "1") (pinfunction "1_1") (pintype "passive"))
      (node (ref "B3") (pin "1") (pinfunction "1_1") (pintype "passive"))
      (node (ref "B4") (pin "1") (pinfunction "1_1") (pintype "passive"))
      (node (ref "B5") (pin "1") (pinfunction "1_1") (pintype "passive"))
      (node (ref "B6") (pin "1") (pinfunction "1_1") (pintype "passive"))
      (node (ref "B7") (pin "1") (pinfunction "1_1") (pintype "passive"))
      (node (ref "C60") (pin "+") (pinfunction "+_+") (pintype "passive"))
      (node (ref "C7") (pin "1") (pinfunction "1_1") (pintype "passive"))
      (node (ref "GPS>") (pin "1") (pinfunction "1_1") (pintype "passive"))
      (node (ref "IC6") (pin "TAB") (pinfunction "OUT_TAB") (pintype "passive"))
      (node (ref "PR0>") (pin "4") (pinfunction "4_4") (pintype "passive"))
      (node (ref "Q2") (pin "C") (pinfunction "C_C") (pintype "passive"))
      (node (ref "R1") (pin "1") (pinfunction "1_1") (pintype "passive"))
      (node (ref "R2") (pin "1") (pinfunction "1_1") (pintype "passive"))
      (node (ref "R23") (pin "1") (pinfunction "1_1") (pintype "passive"))
      (node (ref "R24") (pin "1") (pinfunction "1_1") (pintype "passive"))
      (node (ref "R4") (pin "1") (pinfunction "1_1") (pintype "passive"))
      (node (ref "R47") (pin "1") (pinfunction "1_1") (pintype "passive"))
      (node (ref "R57") (pin "1") (pinfunction "1_1") (pintype "passive"))
      (node (ref "S2") (pin "P$3") (pinfunction "S_P$3") (pintype "passive"))
      (node (ref "S2") (pin "P$4") (pinfunction "S1_P$4") (pintype "passive"))
      (node (ref "S3") (pin "P$3") (pinfunction "S_P$3") (pintype "passive"))
      (node (ref "S3") (pin "P$4") (pinfunction "S1_P$4") (pintype "passive"))
      (node (ref "S4") (pin "P$3") (pinfunction "S_P$3") (pintype "passive"))
      (node (ref "S4") (pin "P$4") (pinfunction "S1_P$4") (pintype "passive"))
      (node (ref "S5") (pin "P$3") (pinfunction "S_P$3") (pintype "passive"))
      (node (ref "S5") (pin "P$4") (pinfunction "S1_P$4") (pintype "passive"))
      (node (ref "U2") (pin "48") (pinfunction "VDD_USB_48") (pintype "power_in"))
      (node (ref "U3") (pin "4") (pinfunction "N_RST_4") (pintype "input"))
    )
    (net (code "2") (name "+5V") (class "Default")
      (node (ref "FB1") (pin "2") (pinfunction "2_2") (pintype "passive"))
      (node (ref "J1") (pin "VBUS") (pinfunction "VBUS_VBUS") (pintype "power_in"))
      (node (ref "R29") (pin "1") (pinfunction "1_1") (pintype "passive"))
      (node (ref "U3") (pin "1") (pinfunction "VDD_1") (pintype "power_in"))
      (node (ref "U4") (pin "5") (pinfunction "VCC_5") (pintype "power_in"))
    )
    (net (code "3") (name "+12V") (class "Default")
      (node (ref "C54") (pin "+") (pinfunction "+_+") (pintype "passive"))
      (node (ref "IC3") (pin "TAB") (pinfunction "OUT_TAB") (pintype "passive"))
      (node (ref "R53") (pin "1") (pinfunction "1_1") (pintype "passive"))
      (node (ref "U$2") (pin "2") (pinfunction "DRAIN_VOLTAGE_2") (pintype "bidirectional"))
    )
    (net (code "4") (name "/10V_INTERMEDIATE") (class "Default")
      (node (ref "C57") (pin "+") (pinfunction "+_+") (pintype "passive"))
      (node (ref "C59") (pin "+") (pinfunction "+_+") (pintype "passive"))
      (node (ref "IC5") (pin "TAB") (pinfunction "OUT_TAB") (pintype "passive"))
      (node (ref "IC6") (pin "2") (pinfunction "IN_2") (pintype "input"))
      (node (ref "R55") (pin "1") (pinfunction "1_1") (pintype "passive"))
    )
    (net (code "5") (name "/ANT_N") (class "Default")
      (node (ref "C29") (pin "1") (pinfunction "1_1") (pintype "passive"))
      (node (ref "L1") (pin "2") (pinfunction "2_2") (pintype "passive"))
      (node (ref "L2") (pin "2") (pinfunction "2_2") (pintype "passive"))
      (node (ref "U$1") (pin "3") (pinfunction "ANTN_3") (pintype "output"))
    )
    (net (code "6") (name "/ANT_P") (class "Default")
      (node (ref "C30") (pin "2") (pinfunction "2_2") (pintype "passive"))
      (node (ref "L3") (pin "1") (pinfunction "1_1") (pintype "passive"))
      (node (ref "L4") (pin "2") (pinfunction "2_2") (pintype "passive"))
      (node (ref "U$1") (pin "2") (pinfunction "ANTP_2") (pintype "output"))
    )
    (net (code "7") (name "/BAT_ADC") (class "Default")
      (node (ref "BAT_ADC") (pin "TP") (pinfunction "TP_TP") (pintype "input"))
      (node (ref "R60") (pin "1") (pinfunction "1_1") (pintype "passive"))
      (node (ref "R61") (pin "2") (pinfunction "2_2") (pintype "passive"))
      (node (ref "U2") (pin "15") (pinfunction "PA1_15") (pintype "bidirectional"))
    )
    (net (code "8") (name "/BAT_PACK_POS") (class "Default")
      (node (ref "BAT") (pin "1") (pinfunction "1_1") (pintype "passive"))
      (node (ref "BAT_PACK_POS") (pin "TP") (pinfunction "TP_TP") (pintype "input"))
      (node (ref "C51") (pin "+") (pinfunction "+_+") (pintype "passive"))
      (node (ref "C52") (pin "+") (pinfunction "+_+") (pintype "passive"))
      (node (ref "D10") (pin "C") (pinfunction "C_C") (pintype "passive"))
      (node (ref "JP3") (pin "1") (pinfunction "1_1") (pintype "passive"))
      (node (ref "R30") (pin "1") (pinfunction "1_1") (pintype "passive"))
      (node (ref "R34") (pin "1") (pinfunction "1_1") (pintype "passive"))
      (node (ref "R51") (pin "2") (pinfunction "2_2") (pintype "passive"))
    )
    (net (code "9") (name "/BTN_1") (class "Default")
      (node (ref "BTN_1") (pin "TP") (pinfunction "TP_TP") (pintype "input"))
      (node (ref "D2") (pin "A") (pinfunction "A_A") (pintype "passive"))
      (node (ref "R6") (pin "2") (pinfunction "2_2") (pintype "passive"))
      (node (ref "R7") (pin "1") (pinfunction "1_1") (pintype "passive"))
      (node (ref "S2") (pin "P$1") (pinfunction "P_P$1") (pintype "passive"))
      (node (ref "S2") (pin "P$2") (pinfunction "P1_P$2") (pintype "passive"))
      (node (ref "U2") (pin "33") (pinfunction "PB12_33") (pintype "bidirectional"))
    )
    (net (code "10") (name "/BTN_2") (class "Default")
      (node (ref "BTN_2") (pin "TP") (pinfunction "TP_TP") (pintype "input"))
      (node (ref "D3") (pin "A") (pinfunction "A_A") (pintype "passive"))
      (node (ref "R5") (pin "2") (pinfunction "2_2") (pintype "passive"))
      (node (ref "R8") (pin "1") (pinfunction "1_1") (pintype "passive"))
      (node (ref "S3") (pin "P$1") (pinfunction "P_P$1") (pintype "passive"))
      (node (ref "S3") (pin "P$2") (pinfunction "P1_P$2") (pintype "passive"))
      (node (ref "U2") (pin "38") (pinfunction "PC7_38") (pintype "bidirectional"))
    )
    (net (code "11") (name "/BTN_3") (class "Default")
      (node (ref "BTN_3") (pin "TP") (pinfunction "TP_TP") (pintype "input"))
      (node (ref "D4") (pin "A") (pinfunction "A_A") (pintype "passive"))
      (node (ref "R12") (pin "2") (pinfunction "2_2") (pintype "passive"))
      (node (ref "R13") (pin "1") (pinfunction "1_1") (pintype "passive"))
      (node (ref "S4") (pin "P$1") (pinfunction "P_P$1") (pintype "passive"))
      (node (ref "S4") (pin "P$2") (pinfunction "P1_P$2") (pintype "passive"))
      (node (ref "U2") (pin "39") (pinfunction "PC8_39") (pintype "bidirectional"))
    )
    (net (code "12") (name "/BTN_4") (class "Default")
      (node (ref "BTN_4") (pin "TP") (pinfunction "TP_TP") (pintype "input"))
      (node (ref "D5") (pin "A") (pinfunction "A_A") (pintype "passive"))
      (node (ref "R16") (pin "2") (pinfunction "2_2") (pintype "passive"))
      (node (ref "R17") (pin "1") (pinfunction "1_1") (pintype "passive"))
      (node (ref "S5") (pin "P$1") (pinfunction "P_P$1") (pintype "passive"))
      (node (ref "S5") (pin "P$2") (pinfunction "P1_P$2") (pintype "passive"))
      (node (ref "U2") (pin "40") (pinfunction "PC9_40") (pintype "bidirectional"))
    )
    (net (code "13") (name "/BT_HCI_RXD") (class "Default")
      (node (ref "BT_RX") (pin "TP") (pinfunction "TP_TP") (pintype "input"))
      (node (ref "CONFIG_INTERFACE_TEST_POINT") (pin "3") (pinfunction "3_3") (pintype "passive"))
      (node (ref "IC2") (pin "22") (pinfunction "HCI_RXD_22") (pintype "bidirectional"))
      (node (ref "U2") (pin "42") (pinfunction "PA9_42") (pintype "bidirectional"))
    )
    (net (code "14") (name "/BT_HCI_TXD") (class "Default")
      (node (ref "BT_TX") (pin "TP") (pinfunction "TP_TP") (pintype "input"))
      (node (ref "CONFIG_INTERFACE_TEST_POINT") (pin "4") (pinfunction "4_4") (pintype "passive"))
      (node (ref "IC2") (pin "23") (pinfunction "HCI_TXD_23") (pintype "bidirectional"))
      (node (ref "U2") (pin "43") (pinfunction "PA10_43") (pintype "bidirectional"))
    )
    (net (code "15") (name "/BT_NRST") (class "Default")
      (node (ref "IC2") (pin "21") (pinfunction "RST_N_21") (pintype "bidirectional"))
      (node (ref "R3") (pin "2") (pinfunction "2_2") (pintype "passive"))
      (node (ref "U1") (pin "1") (pinfunction "VOUT_1") (pintype "passive"))
    )
    (net (code "16") (name "/BT_P2_0_MODE") (class "Default")
      (node (ref "CONFIG_INTERFACE_TEST_POINT") (pin "1") (pinfunction "1_1") (pintype "passive"))
      (node (ref "IC2") (pin "18") (pinfunction "P2_0/MODE_18") (pintype "bidirectional"))
    )
    (net (code "17") (name "/CHARGER_CH_PRECH") (class "Default")
      (node (ref "Q7") (pin "1") (pinfunction "G_1") (pintype "passive"))
      (node (ref "U2") (pin "54") (pinfunction "PD2_54") (pintype "bidirectional"))
    )
    (net (code "18") (name "/CHARGER_SS") (class "Default")
      (node (ref "U$3") (pin "6") (pinfunction "S/S_6") (pintype "bidirectional"))
      (node (ref "U2") (pin "53") (pinfunction "PC12_53") (pintype "bidirectional"))
    )
    (net (code "19") (name "/GPS_EXTINT") (class "Default")
      (node (ref "<GPS") (pin "5") (pinfunction "5_5") (pintype "passive"))
      (node (ref "GPS>") (pin "5") (pinfunction "5_5") (pintype "passive"))
      (node (ref "IC1") (pin "19") (pinfunction "EXTINT_19") (pintype "bidirectional"))
      (node (ref "U2") (pin "36") (pinfunction "PB15_36") (pintype "bidirectional"))
    )
    (net (code "20") (name "/GPS_NRESET") (class "Default")
      (node (ref "<GPS") (pin "6") (pinfunction "6_6") (pintype "passive"))
      (node (ref "GPS>") (pin "6") (pinfunction "6_6") (pintype "passive"))
      (node (ref "IC1") (pin "18") (pinfunction "RESET_N_18") (pintype "bidirectional"))
      (node (ref "U2") (pin "37") (pinfunction "PC6_37") (pintype "bidirectional"))
    )
    (net (code "21") (name "/GPS_RXD") (class "Default")
      (node (ref "<GPS") (pin "7") (pinfunction "7_7") (pintype "passive"))
      (node (ref "GPS>") (pin "7") (pinfunction "7_7") (pintype "passive"))
      (node (ref "IC1") (pin "14") (pinfunction "RXD_14") (pintype "bidirectional"))
      (node (ref "U2") (pin "51") (pinfunction "PC10_51") (pintype "bidirectional"))
    )
    (net (code "22") (name "/GPS_SCL") (class "Default")
      (node (ref "<GPS") (pin "3") (pinfunction "3_3") (pintype "passive"))
      (node (ref "GPS>") (pin "3") (pinfunction "3_3") (pintype "passive"))
      (node (ref "IC1") (pin "12") (pinfunction "SCL_12") (pintype "bidirectional"))
      (node (ref "R1") (pin "2") (pinfunction "2_2") (pintype "passive"))
      (node (ref "U2") (pin "34") (pinfunction "PB13_34") (pintype "bidirectional"))
    )
    (net (code "23") (name "/GPS_SDA") (class "Default")
      (node (ref "<GPS") (pin "4") (pinfunction "4_4") (pintype "passive"))
      (node (ref "GPS>") (pin "4") (pinfunction "4_4") (pintype "passive"))
      (node (ref "IC1") (pin "9") (pinfunction "SDA_9") (pintype "bidirectional"))
      (node (ref "R2") (pin "2") (pinfunction "2_2") (pintype "passive"))
      (node (ref "U2") (pin "35") (pinfunction "PB14_35") (pintype "bidirectional"))
    )
    (net (code "24") (name "/GPS_TXD") (class "Default")
      (node (ref "<GPS") (pin "8") (pinfunction "8_8") (pintype "passive"))
      (node (ref "GPS>") (pin "8") (pinfunction "8_8") (pintype "passive"))
      (node (ref "IC1") (pin "13") (pinfunction "TXD_13") (pintype "bidirectional"))
      (node (ref "U2") (pin "52") (pinfunction "PC11_52") (pintype "bidirectional"))
    )
    (net (code "25") (name "/IND_LED_B") (class "Default")
      (node (ref "R11") (pin "2") (pinfunction "2_2") (pintype "passive"))
      (node (ref "U2") (pin "26") (pinfunction "PB0_26") (pintype "bidirectional"))
    )
    (net (code "26") (name "/IND_LED_G") (class "Default")
      (node (ref "R10") (pin "2") (pinfunction "2_2") (pintype "passive"))
      (node (ref "U2") (pin "25") (pinfunction "PC5_25") (pintype "bidirectional"))
    )
    (net (code "27") (name "/IND_LED_R") (class "Default")
      (node (ref "R15") (pin "2") (pinfunction "2_2") (pintype "passive"))
      (node (ref "U2") (pin "28") (pinfunction "PB2_28") (pintype "bidirectional"))
    )
    (net (code "28") (name "/IND_LED_W") (class "Default")
      (node (ref "R14") (pin "2") (pinfunction "2_2") (pintype "passive"))
      (node (ref "U2") (pin "27") (pinfunction "PB1_27") (pintype "bidirectional"))
    )
    (net (code "29") (name "/INT_POWER") (class "Default")
      (node (ref "C21") (pin "2") (pinfunction "2_2") (pintype "passive"))
      (node (ref "C22") (pin "2") (pinfunction "2_2") (pintype "passive"))
      (node (ref "C23") (pin "2") (pinfunction "2_2") (pintype "passive"))
      (node (ref "C25") (pin "2") (pinfunction "2_2") (pintype "passive"))
      (node (ref "C26") (pin "2") (pinfunction "2_2") (pintype "passive"))
      (node (ref "C27") (pin "2") (pinfunction "2_2") (pintype "passive"))
      (node (ref "C29") (pin "2") (pinfunction "2_2") (pintype "passive"))
      (node (ref "C30") (pin "1") (pinfunction "1_1") (pintype "passive"))
      (node (ref "L2") (pin "1") (pinfunction "1_1") (pintype "passive"))
      (node (ref "L3") (pin "2") (pinfunction "2_2") (pintype "passive"))
      (node (ref "U$1") (pin "1") (pinfunction "VDD1_1") (pintype "power_in"))
      (node (ref "U$1") (pin "17") (pinfunction "VREG_17") (pintype "power_in"))
      (node (ref "U$1") (pin "4") (pinfunction "VDD2_4") (pintype "power_in"))
    )
    (net (code "30") (name "/MCU_WAKEUP") (class "Default")
      (node (ref "D2") (pin "C") (pinfunction "C_C") (pintype "passive"))
      (node (ref "D3") (pin "C") (pinfunction "C_C") (pintype "passive"))
      (node (ref "D4") (pin "C") (pinfunction "C_C") (pintype "passive"))
      (node (ref "D5") (pin "C") (pinfunction "C_C") (pintype "passive"))
      (node (ref "D8") (pin "C") (pinfunction "C_C") (pintype "passive"))
      (node (ref "D9") (pin "C") (pinfunction "C_C") (pintype "passive"))
      (node (ref "U2") (pin "14") (pinfunction "PA0_14") (pintype "bidirectional"))
    )
    (net (code "31") (name "/N$14") (class "Default")
      (node (ref "U2") (pin "41") (pinfunction "PA8_41") (pintype "bidirectional"))
    )
    (net (code "32") (name "/N$78") (class "Default")
      (node (ref "B4") (pin "2") (pinfunction "2_2") (pintype "passive"))
      (node (ref "CONFIG_INTERFACE_TEST_POINT") (pin "2") (pinfunction "2_2") (pintype "passive"))
    )
    (net (code "33") (name "/NRST") (class "Default")
      (node (ref "BTN_NRST") (pin "TP") (pinfunction "TP_TP") (pintype "input"))
      (node (ref "NRST_MCU") (pin "TP") (pinfunction "TP_TP") (pintype "input"))
      (node (ref "PR0>") (pin "5") (pinfunction "5_5") (pintype "passive"))
      (node (ref "R4") (pin "2") (pinfunction "2_2") (pintype "passive"))
      (node (ref "R59") (pin "2") (pinfunction "2_2") (pintype "passive"))
      (node (ref "S1") (pin "P$3") (pinfunction "S_P$3") (pintype "passive"))
      (node (ref "S1") (pin "P$4") (pinfunction "S1_P$4") (pintype "passive"))
      (node (ref "U2") (pin "7") (pinfunction "NRST_7") (pintype "bidirectional"))
    )
    (net (code "34") (name "/POW_LED_G1") (class "Default")
      (node (ref "R20") (pin "1") (pinfunction "1_1") (pintype "passive"))
      (node (ref "U2") (pin "22") (pinfunction "PA6_22") (pintype "bidirectional"))
    )
    (net (code "35") (name "/POW_LED_G2") (class "Default")
      (node (ref "R19") (pin "1") (pinfunction "1_1") (pintype "passive"))
      (node (ref "U2") (pin "21") (pinfunction "PA5_21") (pintype "bidirectional"))
    )
    (net (code "36") (name "/POW_LED_G3") (class "Default")
      (node (ref "R18") (pin "1") (pinfunction "1_1") (pintype "passive"))
      (node (ref "U2") (pin "20") (pinfunction "PA4_20") (pintype "bidirectional"))
    )
    (net (code "37") (name "/POW_LED_R") (class "Default")
      (node (ref "R21") (pin "1") (pinfunction "1_1") (pintype "passive"))
      (node (ref "U2") (pin "24") (pinfunction "PC4_24") (pintype "bidirectional"))
    )
    (net (code "38") (name "/POW_LED_Y") (class "Default")
      (node (ref "R22") (pin "1") (pinfunction "1_1") (pintype "passive"))
      (node (ref "U2") (pin "23") (pinfunction "PA7_23") (pintype "bidirectional"))
    )
    (net (code "39") (name "/RESERVED") (class "Default")
      (node (ref "U2") (pin "30") (pinfunction "PB11_30") (pintype "bidirectional"))
    )
    (net (code "40") (name "/RF_SIGNAL") (class "Default")
      (node (ref "C37") (pin "2") (pinfunction "2_2") (pintype "passive"))
      (node (ref "L7") (pin "2") (pinfunction "2_2") (pintype "passive"))
      (node (ref "RF_SIGNAL") (pin "TP") (pinfunction "TP_TP") (pintype "input"))
      (node (ref "U$2") (pin "1") (pinfunction "RF_IN_1") (pintype "bidirectional"))
    )
    (net (code "41") (name "/RF_SIGNAL_AMPLIFIED") (class "Default")
      (node (ref "J3") (pin "S") (pinfunction "OUT_S") (pintype "bidirectional"))
      (node (ref "U$2") (pin "4") (pinfunction "RF_OUT_4") (pintype "bidirectional"))
    )
    (net (code "42") (name "/SPI2_CLK") (class "Default")
      (node (ref "SPI2_CLK") (pin "TP") (pinfunction "TP_TP") (pintype "input"))
      (node (ref "U$1") (pin "9") (pinfunction "CLK_9") (pintype "input"))
      (node (ref "U2") (pin "29") (pinfunction "PB10_29") (pintype "bidirectional"))
    )
    (net (code "43") (name "/SPI2_IRQ") (class "Default")
      (node (ref "SPI2_IRQ") (pin "TP") (pinfunction "TP_TP") (pintype "input"))
      (node (ref "U$1") (pin "14") (pinfunction "IRQ_14") (pintype "output"))
      (node (ref "U2") (pin "8") (pinfunction "PC0_8") (pintype "bidirectional"))
    )
    (net (code "44") (name "/SPI2_MISO") (class "Default")
      (node (ref "SPI2_MISO") (pin "TP") (pinfunction "TP_TP") (pintype "input"))
      (node (ref "U$1") (pin "10") (pinfunction "MISO_SDO_10") (pintype "output"))
      (node (ref "U2") (pin "10") (pinfunction "PC2_10") (pintype "bidirectional"))
    )
    (net (code "45") (name "/SPI2_MOSI") (class "Default")
      (node (ref "SPI2_MOSI") (pin "TP") (pinfunction "TP_TP") (pintype "input"))
      (node (ref "U$1") (pin "12") (pinfunction "MOSI_SDI_12") (pintype "input"))
      (node (ref "U2") (pin "11") (pinfunction "PC3_11") (pintype "bidirectional"))
    )
    (net (code "46") (name "/SPI2_SEL_RFTX") (class "Default")
      (node (ref "SPI2_SEL_RFTX") (pin "TP") (pinfunction "TP_TP") (pintype "input"))
      (node (ref "U$1") (pin "8") (pinfunction "SEL_8") (pintype "input"))
      (node (ref "U2") (pin "9") (pinfunction "PC1_9") (pintype "bidirectional"))
    )
    (net (code "47") (name "/SWDCLK") (class "Default")
      (node (ref "PR0>") (pin "3") (pinfunction "3_3") (pintype "passive"))
      (node (ref "U2") (pin "49") (pinfunction "PA14_49") (pintype "bidirectional"))
    )
    (net (code "48") (name "/SWDIO") (class "Default")
      (node (ref "PR0>") (pin "2") (pinfunction "2_2") (pintype "passive"))
      (node (ref "U2") (pin "46") (pinfunction "PA13_46") (pintype "bidirectional"))
    )
    (net (code "49") (name "/SWD_RX") (class "Default")
      (node (ref "U3") (pin "12") (pinfunction "RX_12") (pintype "input"))
    )
    (net (code "50") (name "/SWD_RXD") (class "Default")
      (node (ref "SWD_RXD") (pin "TP") (pinfunction "TP_TP") (pintype "input"))
      (node (ref "U2") (pin "16") (pinfunction "PA2_16") (pintype "bidirectional"))
    )
    (net (code "51") (name "/SWD_TX") (class "Default")
      (node (ref "U3") (pin "10") (pinfunction "TX_10") (pintype "output"))
    )
    (net (code "52") (name "/SWD_TXD") (class "Default")
      (node (ref "SWD_TXD") (pin "TP") (pinfunction "TP_TP") (pintype "input"))
      (node (ref "U2") (pin "17") (pinfunction "PA3_17") (pintype "bidirectional"))
    )
    (net (code "53") (name "/USB_DATA_N") (class "Default")
      (node (ref "J2") (pin "D-") (pinfunction "D-_D-") (pintype "bidirectional"))
      (node (ref "U2") (pin "44") (pinfunction "PA11_44") (pintype "bidirectional"))
      (node (ref "U4") (pin "1") (pinfunction "IO1_1") (pintype "bidirectional"))
    )
    (net (code "54") (name "/USB_DATA_P") (class "Default")
      (node (ref "J2") (pin "D+") (pinfunction "D+_D+") (pintype "bidirectional"))
      (node (ref "R27") (pin "2") (pinfunction "2_2") (pintype "passive"))
      (node (ref "U2") (pin "45") (pinfunction "PA12_45") (pintype "bidirectional"))
      (node (ref "U4") (pin "2") (pinfunction "IO2_2") (pintype "bidirectional"))
    )
    (net (code "55") (name "/V+STM") (class "Default")
      (node (ref "B1") (pin "2") (pinfunction "2_2") (pintype "passive"))
      (node (ref "C10") (pin "2") (pinfunction "2_2") (pintype "passive"))
      (node (ref "C16") (pin "2") (pinfunction "2_2") (pintype "passive"))
      (node (ref "C4") (pin "1") (pinfunction "1_1") (pintype "passive"))
      (node (ref "C5") (pin "2") (pinfunction "2_2") (pintype "passive"))
      (node (ref "C6") (pin "2") (pinfunction "2_2") (pintype "passive"))
      (node (ref "C8") (pin "1") (pinfunction "1_1") (pintype "passive"))
      (node (ref "C9") (pin "1") (pinfunction "1_1") (pintype "passive"))
      (node (ref "U2") (pin "1") (pinfunction "VLCD_1") (pintype "power_in"))
      (node (ref "U2") (pin "13") (pinfunction "VDDA_13") (pintype "power_in"))
      (node (ref "U2") (pin "19") (pinfunction "VDD_2_19") (pintype "power_in"))
      (node (ref "U2") (pin "32") (pinfunction "VDD_3_32") (pintype "power_in"))
      (node (ref "U2") (pin "64") (pinfunction "VDD_64") (pintype "power_in"))
    )
    (net (code "56") (name "/VIBRATOR") (class "Default")
      (node (ref "Q3") (pin "1") (pinfunction "G_1") (pintype "passive"))
      (node (ref "R25") (pin "1") (pinfunction "1_1") (pintype "passive"))
      (node (ref "U2") (pin "50") (pinfunction "PA15_50") (pintype "bidirectional"))
    )
    (net (code "57") (name "GND") (class "Default")
      (node (ref "<GPS") (pin "2") (pinfunction "2_2") (pintype "passive"))
      (node (ref "C1") (pin "2") (pinfunction "2_2") (pintype "passive"))
      (node (ref "C10") (pin "1") (pinfunction "1_1") (pintype "passive"))
      (node (ref "C11") (pin "1") (pinfunction "1_1") (pintype "passive"))
      (node (ref "C12") (pin "1") (pinfunction "1_1") (pintype "passive"))
      (node (ref "C13") (pin "1") (pinfunction "1_1") (pintype "passive"))
      (node (ref "C14") (pin "2") (pinfunction "2_2") (pintype "passive"))
      (node (ref "C15") (pin "2") (pinfunction "2_2") (pintype "passive"))
      (node (ref "C16") (pin "1") (pinfunction "1_1") (pintype "passive"))
      (node (ref "C17") (pin "1") (pinfunction "1_1") (pintype "passive"))
      (node (ref "C18") (pin "1") (pinfunction "1_1") (pintype "passive"))
      (node (ref "C19") (pin "2") (pinfunction "22_2") (pintype "passive"))
      (node (ref "C2") (pin "2") (pinfunction "2_2") (pintype "passive"))
      (node (ref "C20") (pin "2") (pinfunction "2_2") (pintype "passive"))
      (node (ref "C21") (pin "1") (pinfunction "1_1") (pintype "passive"))
      (node (ref "C22") (pin "1") (pinfunction "1_1") (pintype "passive"))
      (node (ref "C23") (pin "1") (pinfunction "1_1") (pintype "passive"))
      (node (ref "C24") (pin "1") (pinfunction "1_1") (pintype "passive"))
      (node (ref "C25") (pin "1") (pinfunction "1_1") (pintype "passive"))
      (node (ref "C26") (pin "1") (pinfunction "1_1") (pintype "passive"))
      (node (ref "C27") (pin "1") (pinfunction "1_1") (pintype "passive"))
      (node (ref "C3") (pin "2") (pinfunction "2_2") (pintype "passive"))
      (node (ref "C32") (pin "1") (pinfunction "1_1") (pintype "passive"))
      (node (ref "C33") (pin "2") (pinfunction "2_2") (pintype "passive"))
      (node (ref "C34") (pin "1") (pinfunction "1_1") (pintype "passive"))
      (node (ref "C36") (pin "1") (pinfunction "1_1") (pintype "passive"))
      (node (ref "C37") (pin "1") (pinfunction "1_1") (pintype "passive"))
      (node (ref "C4") (pin "2") (pinfunction "2_2") (pintype "passive"))
      (node (ref "C47") (pin "1") (pinfunction "1_1") (pintype "passive"))
      (node (ref "C48") (pin "-") (pinfunction "-_-") (pintype "passive"))
      (node (ref "C49") (pin "1") (pinfunction "1_1") (pintype "passive"))
      (node (ref "C5") (pin "1") (pinfunction "1_1") (pintype "passive"))
      (node (ref "C51") (pin "-") (pinfunction "-_-") (pintype "passive"))
      (node (ref "C52") (pin "-") (pinfunction "-_-") (pintype "passive"))
      (node (ref "C53") (pin "-") (pinfunction "-_-") (pintype "passive"))
      (node (ref "C54") (pin "-") (pinfunction "-_-") (pintype "passive"))
      (node (ref "C55") (pin "-") (pinfunction "-_-") (pintype "passive"))
      (node (ref "C56") (pin "-") (pinfunction "-_-") (pintype "passive"))
      (node (ref "C57") (pin "-") (pinfunction "-_-") (pintype "passive"))
      (node (ref "C58") (pin "-") (pinfunction "-_-") (pintype "passive"))
      (node (ref "C59") (pin "-") (pinfunction "-_-") (pintype "passive"))
      (node (ref "C6") (pin "1") (pinfunction "1_1") (pintype "passive"))
      (node (ref "C60") (pin "-") (pinfunction "-_-") (pintype "passive"))
      (node (ref "C61") (pin "-") (pinfunction "-_-") (pintype "passive"))
      (node (ref "C62") (pin "2") (pinfunction "2_2") (pintype "passive"))
      (node (ref "C7") (pin "2") (pinfunction "2_2") (pintype "passive"))
      (node (ref "C8") (pin "2") (pinfunction "2_2") (pintype "passive"))
      (node (ref "C9") (pin "2") (pinfunction "2_2") (pintype "passive"))
      (node (ref "CONFIG_INTERFACE_TEST_POINT") (pin "5") (pinfunction "5_5") (pintype "passive"))
      (node (ref "D6") (pin "A") (pinfunction "A_A") (pintype "passive"))
      (node (ref "FB3") (pin "1") (pinfunction "1_1") (pintype "passive"))
      (node (ref "FB4") (pin "1") (pinfunction "1_1") (pintype "passive"))
      (node (ref "GPS>") (pin "2") (pinfunction "2_2") (pintype "passive"))
      (node (ref "IC1") (pin "1") (pinfunction "GND_1") (pintype "bidirectional"))
      (node (ref "IC1") (pin "10") (pinfunction "GND_10") (pintype "bidirectional"))
      (node (ref "IC1") (pin "11") (pinfunction "GND_11") (pintype "bidirectional"))
      (node (ref "IC1") (pin "15") (pinfunction "GND_15") (pintype "bidirectional"))
      (node (ref "IC1") (pin "16") (pinfunction "GND_16") (pintype "bidirectional"))
      (node (ref "IC1") (pin "20") (pinfunction "GND_20") (pintype "bidirectional"))
      (node (ref "IC1") (pin "4") (pinfunction "GND_4") (pintype "bidirectional"))
      (node (ref "IC1") (pin "5") (pinfunction "GND_5") (pintype "bidirectional"))
      (node (ref "IC1") (pin "6") (pinfunction "GND_6") (pintype "bidirectional"))
      (node (ref "IC2") (pin "1") (pinfunction "GND(1)_1") (pintype "bidirectional"))
      (node (ref "IC2") (pin "2") (pinfunction "GND(2)_2") (pintype "bidirectional"))
      (node (ref "IC2") (pin "3") (pinfunction "GND(3)_3") (pintype "bidirectional"))
      (node (ref "IC2") (pin "31") (pinfunction "GND(4)_31") (pintype "bidirectional"))
      (node (ref "IC2") (pin "32") (pinfunction "GND(5)_32") (pintype "bidirectional"))
      (node (ref "IC2") (pin "33") (pinfunction "GND(6)_33") (pintype "bidirectional"))
      (node (ref "J1") (pin "GND") (pinfunction "GND_GND") (pintype "power_in"))
      (node (ref "J1") (pin "SHIELD1") (pinfunction "SHIELD_SHIELD1") (pintype "bidirectional"))
      (node (ref "J1") (pin "SHIELD2") (pinfunction "SHIELD_SHIELD2") (pintype "bidirectional"))
      (node (ref "J1") (pin "SHIELD3") (pinfunction "SHIELD_SHIELD3") (pintype "bidirectional"))
      (node (ref "J3") (pin "GND") (pinfunction "GND_GND") (pintype "bidirectional"))
      (node (ref "J4") (pin "GND") (pinfunction "GND_GND") (pintype "power_in"))
      (node (ref "J4") (pin "SHIELD1") (pinfunction "SHIELD_SHIELD1") (pintype "bidirectional"))
      (node (ref "J4") (pin "SHIELD2") (pinfunction "SHIELD_SHIELD2") (pintype "bidirectional"))
      (node (ref "J4") (pin "SHIELD3") (pinfunction "SHIELD_SHIELD3") (pintype "bidirectional"))
      (node (ref "L5") (pin "1") (pinfunction "1_1") (pintype "passive"))
      (node (ref "LED10") (pin "C") (pinfunction "C_C") (pintype "passive"))
      (node (ref "LED2") (pin "C") (pinfunction "C_C") (pintype "passive"))
      (node (ref "LED3") (pin "C") (pinfunction "C_C") (pintype "passive"))
      (node (ref "LED4") (pin "C") (pinfunction "C_C") (pintype "passive"))
      (node (ref "LED5") (pin "C") (pinfunction "C_C") (pintype "passive"))
      (node (ref "LED6") (pin "C") (pinfunction "C_C") (pintype "passive"))
      (node (ref "LED7") (pin "C") (pinfunction "C_C") (pintype "passive"))
      (node (ref "LED8") (pin "C") (pinfunction "C_C") (pintype "passive"))
      (node (ref "LED9") (pin "C") (pinfunction "C_C") (pintype "passive"))
      (node (ref "PR0>") (pin "1") (pinfunction "1_1") (pintype "passive"))
      (node (ref "Q3") (pin "2") (pinfunction "S_2") (pintype "passive"))
      (node (ref "Q6") (pin "1") (pinfunction "1_1") (pintype "passive"))
      (node (ref "Q6") (pin "2") (pinfunction "2_2") (pintype "passive"))
      (node (ref "Q6") (pin "3") (pinfunction "3_3") (pintype "passive"))
      (node (ref "Q7") (pin "2") (pinfunction "S_2") (pintype "passive"))
      (node (ref "R13") (pin "2") (pinfunction "2_2") (pintype "passive"))
      (node (ref "R17") (pin "2") (pinfunction "2_2") (pintype "passive"))
      (node (ref "R25") (pin "2") (pinfunction "2_2") (pintype "passive"))
      (node (ref "R26") (pin "2") (pinfunction "2_2") (pintype "passive"))
      (node (ref "R28") (pin "2") (pinfunction "2_2") (pintype "passive"))
      (node (ref "R41") (pin "1") (pinfunction "1_1") (pintype "passive"))
      (node (ref "R44") (pin "2") (pinfunction "2_2") (pintype "passive"))
      (node (ref "R50") (pin "1") (pinfunction "1_1") (pintype "passive"))
      (node (ref "R52") (pin "1") (pinfunction "1_1") (pintype "passive"))
      (node (ref "R54") (pin "2") (pinfunction "2_2") (pintype "passive"))
      (node (ref "R56") (pin "2") (pinfunction "2_2") (pintype "passive"))
      (node (ref "R58") (pin "2") (pinfunction "2_2") (pintype "passive"))
      (node (ref "R61") (pin "1") (pinfunction "1_1") (pintype "passive"))
      (node (ref "R7") (pin "2") (pinfunction "2_2") (pintype "passive"))
      (node (ref "R8") (pin "2") (pinfunction "2_2") (pintype "passive"))
      (node (ref "S1") (pin "P$1") (pinfunction "P_P$1") (pintype "passive"))
      (node (ref "S1") (pin "P$2") (pinfunction "P1_P$2") (pintype "passive"))
      (node (ref "U$1") (pin "PAD") (pinfunction "GND_PAD_PAD") (pintype "power_in"))
      (node (ref "U$2") (pin "5_L") (pinfunction "RF_GND_L_5_L") (pintype "bidirectional"))
      (node (ref "U$2") (pin "5_R") (pinfunction "RF_GND_R_5_R") (pintype "bidirectional"))
      (node (ref "U$3") (pin "4") (pinfunction "GND_4") (pintype "bidirectional"))
      (node (ref "U1") (pin "2") (pinfunction "VDD_2") (pintype "passive"))
      (node (ref "U2") (pin "12") (pinfunction "VSSA_12") (pintype "power_in"))
      (node (ref "U2") (pin "18") (pinfunction "VSS_2_18") (pintype "power_in"))
      (node (ref "U2") (pin "31") (pinfunction "VSS_3_31") (pintype "power_in"))
      (node (ref "U2") (pin "47") (pinfunction "VSS_4_47") (pintype "power_in"))
      (node (ref "U2") (pin "60") (pinfunction "BOOT0_60") (pintype "input"))
      (node (ref "U2") (pin "63") (pinfunction "VSS_63") (pintype "power_in"))
      (node (ref "U3") (pin "20") (pinfunction "VSS_20") (pintype "power_in"))
      (node (ref "U4") (pin "3") (pinfunction "GND_3") (pintype "passive"))
    )
    (net (code "58") (name "Net-(B5-Pad2)") (class "Default")
      (node (ref "B5") (pin "2") (pinfunction "2_2") (pintype "passive"))
      (node (ref "D1") (pin "C") (pinfunction "C_C") (pintype "passive"))
      (node (ref "JP2") (pin "1") (pinfunction "1_1") (pintype "passive"))
    )
    (net (code "59") (name "Net-(BAT-Pad2)") (class "Default")
      (node (ref "BAT") (pin "2") (pinfunction "2_2") (pintype "passive"))
      (node (ref "R31") (pin "1") (pinfunction "1_1") (pintype "passive"))
    )
    (net (code "60") (name "Net-(BAT-Pad3)") (class "Default")
      (node (ref "BAT") (pin "3") (pinfunction "3_3") (pintype "passive"))
      (node (ref "R32") (pin "1") (pinfunction "1_1") (pintype "passive"))
    )
    (net (code "61") (name "Net-(BAT-Pad4)") (class "Default")
      (node (ref "BAT") (pin "4") (pinfunction "4_4") (pintype "passive"))
      (node (ref "R33") (pin "1") (pinfunction "1_1") (pintype "passive"))
    )
    (net (code "62") (name "Net-(C11-Pad2)") (class "Default")
      (node (ref "C11") (pin "2") (pinfunction "2_2") (pintype "passive"))
      (node (ref "R59") (pin "1") (pinfunction "1_1") (pintype "passive"))
    )
    (net (code "63") (name "Net-(C12-Pad2)") (class "Default")
      (node (ref "C12") (pin "2") (pinfunction "2_2") (pintype "passive"))
      (node (ref "R6") (pin "1") (pinfunction "1_1") (pintype "passive"))
    )
    (net (code "64") (name "Net-(C13-Pad2)") (class "Default")
      (node (ref "C13") (pin "2") (pinfunction "2_2") (pintype "passive"))
      (node (ref "R5") (pin "1") (pinfunction "1_1") (pintype "passive"))
    )
    (net (code "65") (name "Net-(C15-Pad1)") (class "Default")
      (node (ref "C15") (pin "1") (pinfunction "1_1") (pintype "passive"))
      (node (ref "Q1") (pin "1") (pinfunction "1_1") (pintype "passive"))
      (node (ref "R9") (pin "1") (pinfunction "1_1") (pintype "passive"))
    )
    (net (code "66") (name "Net-(C17-Pad2)") (class "Default")
      (node (ref "C17") (pin "2") (pinfunction "2_2") (pintype "passive"))
      (node (ref "R12") (pin "1") (pinfunction "1_1") (pintype "passive"))
    )
    (net (code "67") (name "Net-(C18-Pad2)") (class "Default")
      (node (ref "C18") (pin "2") (pinfunction "2_2") (pintype "passive"))
      (node (ref "R16") (pin "1") (pinfunction "1_1") (pintype "passive"))
    )
    (net (code "68") (name "Net-(C19-11)") (class "Default")
      (node (ref "C19") (pin "1") (pinfunction "11_1") (pintype "passive"))
      (node (ref "U3") (pin "2") (pinfunction "OSC1_2") (pintype "input"))
    )
    (net (code "69") (name "Net-(C19-33)") (class "Default")
      (node (ref "C19") (pin "3") (pinfunction "33_3") (pintype "passive"))
      (node (ref "U3") (pin "3") (pinfunction "OSC2_3") (pintype "output"))
    )
    (net (code "70") (name "Net-(C28-Pad1)") (class "Default")
      (node (ref "C28") (pin "1") (pinfunction "1_1") (pintype "passive"))
      (node (ref "L4") (pin "1") (pinfunction "1_1") (pintype "passive"))
    )
    (net (code "71") (name "Net-(C28-Pad2)") (class "Default")
      (node (ref "C28") (pin "2") (pinfunction "2_2") (pintype "passive"))
      (node (ref "C33") (pin "1") (pinfunction "1_1") (pintype "passive"))
      (node (ref "C35") (pin "2") (pinfunction "2_2") (pintype "passive"))
      (node (ref "L5") (pin "2") (pinfunction "2_2") (pintype "passive"))
    )
    (net (code "72") (name "Net-(C31-Pad1)") (class "Default")
      (node (ref "C31") (pin "1") (pinfunction "1_1") (pintype "passive"))
      (node (ref "L1") (pin "1") (pinfunction "1_1") (pintype "passive"))
    )
    (net (code "73") (name "Net-(C31-Pad2)") (class "Default")
      (node (ref "C31") (pin "2") (pinfunction "2_2") (pintype "passive"))
      (node (ref "C32") (pin "2") (pinfunction "2_2") (pintype "passive"))
      (node (ref "C34") (pin "2") (pinfunction "2_2") (pintype "passive"))
      (node (ref "L6") (pin "1") (pinfunction "1_1") (pintype "passive"))
    )
    (net (code "74") (name "Net-(C35-Pad1)") (class "Default")
      (node (ref "C35") (pin "1") (pinfunction "1_1") (pintype "passive"))
      (node (ref "C36") (pin "2") (pinfunction "2_2") (pintype "passive"))
      (node (ref "L6") (pin "2") (pinfunction "2_2") (pintype "passive"))
      (node (ref "L7") (pin "1") (pinfunction "1_1") (pintype "passive"))
    )
    (net (code "75") (name "Net-(C47-Pad2)") (class "Default")
      (node (ref "C47") (pin "2") (pinfunction "2_2") (pintype "passive"))
      (node (ref "R45") (pin "2") (pinfunction "2_2") (pintype "passive"))
    )
    (net (code "76") (name "Net-(C63-Pad-)") (class "Default")
      (node (ref "C63") (pin "-") (pinfunction "-_-") (pintype "passive"))
      (node (ref "D10") (pin "A") (pinfunction "A_A") (pintype "passive"))
      (node (ref "L8") (pin "3") (pinfunction "3_3") (pintype "passive"))
    )
    (net (code "77") (name "Net-(D6-PadC)") (class "Default")
      (node (ref "D6") (pin "C") (pinfunction "C_C") (pintype "passive"))
      (node (ref "D7") (pin "C") (pinfunction "C_C") (pintype "passive"))
      (node (ref "Q6") (pin "4") (pinfunction "4_4") (pintype "passive"))
      (node (ref "R41") (pin "2") (pinfunction "2_2") (pintype "passive"))
      (node (ref "R42") (pin "1") (pinfunction "1_1") (pintype "passive"))
    )
    (net (code "78") (name "Net-(D7-PadA)") (class "Default")
      (node (ref "D7") (pin "A") (pinfunction "A_A") (pintype "passive"))
      (node (ref "R42") (pin "2") (pinfunction "2_2") (pintype "passive"))
      (node (ref "R43") (pin "2") (pinfunction "2_2") (pintype "passive"))
    )
    (net (code "79") (name "Net-(FB1-Pad1)") (class "Default")
      (node (ref "FB1") (pin "1") (pinfunction "1_1") (pintype "passive"))
      (node (ref "J2") (pin "VBUS") (pinfunction "VBUS_VBUS") (pintype "power_in"))
    )
    (net (code "80") (name "Net-(FB3-Pad2)") (class "Default")
      (node (ref "FB3") (pin "2") (pinfunction "2_2") (pintype "passive"))
      (node (ref "J2") (pin "GND") (pinfunction "GND_GND") (pintype "power_in"))
    )
    (net (code "81") (name "Net-(FB4-Pad2)") (class "Default")
      (node (ref "FB4") (pin "2") (pinfunction "2_2") (pintype "passive"))
      (node (ref "J2") (pin "SHIELD1") (pinfunction "SHIELD_SHIELD1") (pintype "bidirectional"))
      (node (ref "J2") (pin "SHIELD2") (pinfunction "SHIELD_SHIELD2") (pintype "bidirectional"))
      (node (ref "J2") (pin "SHIELD3") (pinfunction "SHIELD_SHIELD3") (pintype "bidirectional"))
    )
    (net (code "82") (name "Net-(IC1-VCC)") (class "Default")
      (node (ref "B2") (pin "2") (pinfunction "2_2") (pintype "passive"))
      (node (ref "C1") (pin "1") (pinfunction "1_1") (pintype "passive"))
      (node (ref "C2") (pin "1") (pinfunction "1_1") (pintype "passive"))
      (node (ref "C3") (pin "1") (pinfunction "1_1") (pintype "passive"))
      (node (ref "C62") (pin "1") (pinfunction "1_1") (pintype "passive"))
      (node (ref "IC1") (pin "17") (pinfunction "VCC_17") (pintype "bidirectional"))
      (node (ref "IC1") (pin "2") (pinfunction "VCC_IO_2") (pintype "bidirectional"))
      (node (ref "IC1") (pin "3") (pinfunction "V_BCKP_3") (pintype "bidirectional"))
    )
    (net (code "83") (name "Net-(IC2-P0_2{slash}LED)") (class "Default")
      (node (ref "IC2") (pin "30") (pinfunction "P0_2/LED_30") (pintype "bidirectional"))
      (node (ref "LED1") (pin "C") (pinfunction "C_C") (pintype "passive"))
    )
    (net (code "84") (name "Net-(IC2-VBAT)") (class "Default")
      (node (ref "B3") (pin "2") (pinfunction "2_2") (pintype "passive"))
      (node (ref "IC2") (pin "4") (pinfunction "VBAT_4") (pintype "bidirectional"))
      (node (ref "LED1") (pin "A") (pinfunction "A_A") (pintype "passive"))
      (node (ref "R3") (pin "1") (pinfunction "1_1") (pintype "passive"))
      (node (ref "U1") (pin "3") (pinfunction "VSS_3") (pintype "passive"))
    )
    (net (code "85") (name "Net-(IC3-ADJ)") (class "Default")
      (node (ref "C55") (pin "+") (pinfunction "+_+") (pintype "passive"))
      (node (ref "IC3") (pin "1") (pinfunction "ADJ_1") (pintype "input"))
      (node (ref "R53") (pin "2") (pinfunction "2_2") (pintype "passive"))
      (node (ref "R54") (pin "1") (pinfunction "1_1") (pintype "passive"))
    )
    (net (code "86") (name "Net-(IC3-IN)") (class "Default")
      (node (ref "C53") (pin "+") (pinfunction "+_+") (pintype "passive"))
      (node (ref "C56") (pin "+") (pinfunction "+_+") (pintype "passive"))
      (node (ref "IC3") (pin "2") (pinfunction "IN_2") (pintype "input"))
      (node (ref "IC5") (pin "2") (pinfunction "IN_2") (pintype "input"))
      (node (ref "JP3") (pin "2") (pinfunction "2_2") (pintype "passive"))
      (node (ref "R60") (pin "2") (pinfunction "2_2") (pintype "passive"))
    )
    (net (code "87") (name "Net-(IC5-ADJ)") (class "Default")
      (node (ref "C58") (pin "+") (pinfunction "+_+") (pintype "passive"))
      (node (ref "IC5") (pin "1") (pinfunction "ADJ_1") (pintype "input"))
      (node (ref "R55") (pin "2") (pinfunction "2_2") (pintype "passive"))
      (node (ref "R56") (pin "1") (pinfunction "1_1") (pintype "passive"))
    )
    (net (code "88") (name "Net-(IC6-ADJ)") (class "Default")
      (node (ref "C61") (pin "+") (pinfunction "+_+") (pintype "passive"))
      (node (ref "IC6") (pin "1") (pinfunction "ADJ_1") (pintype "input"))
      (node (ref "R57") (pin "2") (pinfunction "2_2") (pintype "passive"))
      (node (ref "R58") (pin "1") (pinfunction "1_1") (pintype "passive"))
    )
    (net (code "89") (name "Net-(J4-PadD+)") (class "Default")
      (node (ref "J4") (pin "D+") (pinfunction "D+_D+") (pintype "bidirectional"))
      (node (ref "USB_DP") (pin "TP") (pinfunction "TP_TP") (pintype "input"))
    )
    (net (code "90") (name "Net-(J4-PadD-)") (class "Default")
      (node (ref "J4") (pin "D-") (pinfunction "D-_D-") (pintype "bidirectional"))
      (node (ref "USB_DN") (pin "TP") (pinfunction "TP_TP") (pintype "input"))
    )
    (net (code "91") (name "Net-(J4-PadID)") (class "Default")
      (node (ref "J4") (pin "ID") (pinfunction "ID_ID") (pintype "bidirectional"))
      (node (ref "USB_ID") (pin "TP") (pinfunction "TP_TP") (pintype "input"))
    )
    (net (code "92") (name "Net-(L8-Pad4)") (class "Default")
      (node (ref "L8") (pin "4") (pinfunction "4_4") (pintype "passive"))
      (node (ref "R49") (pin "2") (pinfunction "2_2") (pintype "passive"))
      (node (ref "R50") (pin "2") (pinfunction "2_2") (pintype "passive"))
    )
    (net (code "93") (name "Net-(LED2-PadA)") (class "Default")
      (node (ref "LED2") (pin "A") (pinfunction "A_A") (pintype "passive"))
      (node (ref "R10") (pin "1") (pinfunction "1_1") (pintype "passive"))
    )
    (net (code "94") (name "Net-(LED3-PadA)") (class "Default")
      (node (ref "LED3") (pin "A") (pinfunction "A_A") (pintype "passive"))
      (node (ref "R11") (pin "1") (pinfunction "1_1") (pintype "passive"))
    )
    (net (code "95") (name "Net-(LED4-PadA)") (class "Default")
      (node (ref "LED4") (pin "A") (pinfunction "A_A") (pintype "passive"))
      (node (ref "R14") (pin "1") (pinfunction "1_1") (pintype "passive"))
    )
    (net (code "96") (name "Net-(LED5-PadA)") (class "Default")
      (node (ref "LED5") (pin "A") (pinfunction "A_A") (pintype "passive"))
      (node (ref "R15") (pin "1") (pinfunction "1_1") (pintype "passive"))
    )
    (net (code "97") (name "Net-(LED6-PadA)") (class "Default")
      (node (ref "LED6") (pin "A") (pinfunction "A_A") (pintype "passive"))
      (node (ref "R18") (pin "2") (pinfunction "2_2") (pintype "passive"))
    )
    (net (code "98") (name "Net-(LED7-PadA)") (class "Default")
      (node (ref "LED7") (pin "A") (pinfunction "A_A") (pintype "passive"))
      (node (ref "R19") (pin "2") (pinfunction "2_2") (pintype "passive"))
    )
    (net (code "99") (name "Net-(LED8-PadA)") (class "Default")
      (node (ref "LED8") (pin "A") (pinfunction "A_A") (pintype "passive"))
      (node (ref "R20") (pin "2") (pinfunction "2_2") (pintype "passive"))
    )
    (net (code "100") (name "Net-(LED9-PadA)") (class "Default")
      (node (ref "LED9") (pin "A") (pinfunction "A_A") (pintype "passive"))
      (node (ref "R21") (pin "2") (pinfunction "2_2") (pintype "passive"))
    )
    (net (code "101") (name "Net-(LED10-PadA)") (class "Default")
      (node (ref "LED10") (pin "A") (pinfunction "A_A") (pintype "passive"))
      (node (ref "R22") (pin "2") (pinfunction "2_2") (pintype "passive"))
    )
    (net (code "102") (name "Net-(LED11-PadA)") (class "Default")
      (node (ref "LED11") (pin "A") (pinfunction "A_A") (pintype "passive"))
      (node (ref "R23") (pin "2") (pinfunction "2_2") (pintype "passive"))
    )
    (net (code "103") (name "Net-(LED12-PadA)") (class "Default")
      (node (ref "LED12") (pin "A") (pinfunction "A_A") (pintype "passive"))
      (node (ref "R24") (pin "2") (pinfunction "2_2") (pintype "passive"))
    )
    (net (code "104") (name "Net-(Q2-PadB)") (class "Default")
      (node (ref "Q2") (pin "B") (pinfunction "B_B") (pintype "passive"))
      (node (ref "R28") (pin "1") (pinfunction "1_1") (pintype "passive"))
      (node (ref "R29") (pin "2") (pinfunction "2_2") (pintype "passive"))
    )
    (net (code "105") (name "Net-(Q2-PadE)") (class "Default")
      (node (ref "Q2") (pin "E") (pinfunction "E_E") (pintype "passive"))
      (node (ref "R27") (pin "1") (pinfunction "1_1") (pintype "passive"))
    )
    (net (code "106") (name "Net-(Q3-D)") (class "Default")
      (node (ref "D1") (pin "A") (pinfunction "A_A") (pintype "passive"))
      (node (ref "JP2") (pin "2") (pinfunction "2_2") (pintype "passive"))
      (node (ref "Q3") (pin "3") (pinfunction "D_3") (pintype "passive"))
    )
    (net (code "107") (name "Net-(Q5-Pad1)") (class "Default")
      (node (ref "Q5") (pin "1") (pinfunction "1_1") (pintype "passive"))
      (node (ref "Q5") (pin "2") (pinfunction "2_2") (pintype "passive"))
      (node (ref "Q5") (pin "3") (pinfunction "3_3") (pintype "passive"))
      (node (ref "R36") (pin "1") (pinfunction "1_1") (pintype "passive"))
      (node (ref "R38") (pin "2") (pinfunction "2_2") (pintype "passive"))
      (node (ref "R39") (pin "2") (pinfunction "2_2") (pintype "passive"))
    )
    (net (code "108") (name "Net-(Q5-Pad4)") (class "Default")
      (node (ref "Q5") (pin "4") (pinfunction "4_4") (pintype "passive"))
      (node (ref "R39") (pin "1") (pinfunction "1_1") (pintype "passive"))
      (node (ref "R40") (pin "1") (pinfunction "1_1") (pintype "passive"))
    )
    (net (code "109") (name "Net-(Q5-Pad5)") (class "Default")
      (node (ref "Q5") (pin "5") (pinfunction "5_5") (pintype "passive"))
      (node (ref "Q5") (pin "6") (pinfunction "6_6") (pintype "passive"))
      (node (ref "Q5") (pin "7") (pinfunction "7_7") (pintype "passive"))
      (node (ref "Q5") (pin "8") (pinfunction "8_8") (pintype "passive"))
      (node (ref "Q6") (pin "5") (pinfunction "5_5") (pintype "passive"))
      (node (ref "Q6") (pin "6") (pinfunction "6_6") (pintype "passive"))
      (node (ref "Q6") (pin "7") (pinfunction "7_7") (pintype "passive"))
      (node (ref "Q6") (pin "8") (pinfunction "8_8") (pintype "passive"))
    )
    (net (code "110") (name "Net-(Q7-D)") (class "Default")
      (node (ref "Q7") (pin "3") (pinfunction "D_3") (pintype "passive"))
      (node (ref "R46") (pin "1") (pinfunction "1_1") (pintype "passive"))
    )
    (net (code "111") (name "Net-(R46-Pad2)") (class "Default")
      (node (ref "R46") (pin "2") (pinfunction "2_2") (pintype "passive"))
      (node (ref "R47") (pin "2") (pinfunction "2_2") (pintype "passive"))
      (node (ref "R48") (pin "1") (pinfunction "1_1") (pintype "passive"))
    )
    (net (code "112") (name "Net-(U$1-CLOCK16N)") (class "Default")
      (node (ref "Q4") (pin "1") (pinfunction "1_1") (pintype "passive"))
      (node (ref "U$1") (pin "20") (pinfunction "CLOCK16N_20") (pintype "bidirectional"))
    )
    (net (code "113") (name "Net-(U$1-CLOCK16P)") (class "Default")
      (node (ref "Q4") (pin "2") (pinfunction "2_2") (pintype "passive"))
      (node (ref "U$1") (pin "19") (pinfunction "CLOCK16P_19") (pintype "bidirectional"))
    )
    (net (code "114") (name "Net-(U$1-SYSCLK)") (class "Default")
      (node (ref "RF_SYSCLK") (pin "TP") (pinfunction "TP_TP") (pintype "input"))
      (node (ref "U$1") (pin "7") (pinfunction "SYSCLK_7") (pintype "output"))
    )
    (net (code "115") (name "Net-(U$1-VDD_IO)") (class "Default")
      (node (ref "B6") (pin "2") (pinfunction "2_2") (pintype "passive"))
      (node (ref "C24") (pin "2") (pinfunction "2_2") (pintype "passive"))
      (node (ref "U$1") (pin "15") (pinfunction "VDD_IO_15") (pintype "power_in"))
    )
    (net (code "116") (name "Net-(U$2-GATE_VOLTAGE)") (class "Default")
      (node (ref "B7") (pin "2") (pinfunction "2_2") (pintype "passive"))
      (node (ref "U$2") (pin "3") (pinfunction "GATE_VOLTAGE_3") (pintype "bidirectional"))
    )
    (net (code "117") (name "Net-(U$3-IFB)") (class "Default")
      (node (ref "C49") (pin "2") (pinfunction "2_2") (pintype "passive"))
      (node (ref "R48") (pin "2") (pinfunction "2_2") (pintype "passive"))
      (node (ref "R49") (pin "1") (pinfunction "1_1") (pintype "passive"))
      (node (ref "U$3") (pin "3") (pinfunction "IFB_3") (pintype "bidirectional"))
    )
    (net (code "118") (name "Net-(U$3-VC)") (class "Default")
      (node (ref "R45") (pin "1") (pinfunction "1_1") (pintype "passive"))
      (node (ref "U$3") (pin "1") (pinfunction "VC_1") (pintype "bidirectional"))
    )
    (net (code "119") (name "Net-(U$3-VFB)") (class "Default")
      (node (ref "R51") (pin "1") (pinfunction "1_1") (pintype "passive"))
      (node (ref "R52") (pin "2") (pinfunction "2_2") (pintype "passive"))
      (node (ref "U$3") (pin "2") (pinfunction "VFB_2") (pintype "bidirectional"))
    )
    (net (code "120") (name "Net-(U$3-VIN)") (class "Default")
      (node (ref "C48") (pin "+") (pinfunction "+_+") (pintype "passive"))
      (node (ref "J4") (pin "VBUS") (pinfunction "VBUS_VBUS") (pintype "power_in"))
      (node (ref "L8") (pin "1") (pinfunction "1_1") (pintype "passive"))
      (node (ref "U$3") (pin "7") (pinfunction "VIN_7") (pintype "bidirectional"))
    )
    (net (code "121") (name "Net-(U$3-VSW)") (class "Default")
      (node (ref "C63") (pin "+") (pinfunction "+_+") (pintype "passive"))
      (node (ref "L8") (pin "2") (pinfunction "2_2") (pintype "passive"))
      (node (ref "U$3") (pin "5") (pinfunction "VSW_5") (pintype "bidirectional"))
    )
    (net (code "122") (name "Net-(U2-PH0-OSC_IN)") (class "Default")
      (node (ref "C14") (pin "1") (pinfunction "1_1") (pintype "passive"))
      (node (ref "Q1") (pin "2") (pinfunction "2_2") (pintype "passive"))
      (node (ref "U2") (pin "5") (pinfunction "PH0-OSC_IN_5") (pintype "bidirectional"))
    )
    (net (code "123") (name "Net-(U2-PH1-OSC_OUT)") (class "Default")
      (node (ref "R9") (pin "2") (pinfunction "2_2") (pintype "passive"))
      (node (ref "U2") (pin "6") (pinfunction "PH1-OSC_OUT_6") (pintype "bidirectional"))
    )
    (net (code "124") (name "Net-(U3-D+)") (class "Default")
      (node (ref "J1") (pin "D+") (pinfunction "D+_D+") (pintype "bidirectional"))
      (node (ref "U3") (pin "19") (pinfunction "D+_19") (pintype "bidirectional"))
    )
    (net (code "125") (name "Net-(U3-D-)") (class "Default")
      (node (ref "J1") (pin "D-") (pinfunction "D-_D-") (pintype "bidirectional"))
      (node (ref "U3") (pin "18") (pinfunction "D-_18") (pintype "bidirectional"))
    )
    (net (code "126") (name "Net-(U3-GP6{slash}RXLED)") (class "Default")
      (node (ref "LED11") (pin "C") (pinfunction "C_C") (pintype "passive"))
      (node (ref "U3") (pin "6") (pinfunction "GP6/RXLED_6") (pintype "bidirectional"))
    )
    (net (code "127") (name "Net-(U3-GP7{slash}TXLED)") (class "Default")
      (node (ref "LED12") (pin "C") (pinfunction "C_C") (pintype "passive"))
      (node (ref "U3") (pin "5") (pinfunction "GP7/TXLED_5") (pintype "bidirectional"))
    )
    (net (code "128") (name "Net-(U3-VUSB)") (class "Default")
      (node (ref "C20") (pin "1") (pinfunction "1_1") (pintype "passive"))
      (node (ref "U3") (pin "17") (pinfunction "VUSB_17") (pintype "power_in"))
    )
    (net (code "129") (name "Net-(U4-IO3)") (class "Default")
      (node (ref "J2") (pin "ID") (pinfunction "ID_ID") (pintype "bidirectional"))
      (node (ref "R26") (pin "1") (pinfunction "1_1") (pintype "passive"))
      (node (ref "U4") (pin "4") (pinfunction "IO3_4") (pintype "bidirectional"))
    )
    (net (code "130") (name "Net-(U5-AVDD)") (class "Default")
      (node (ref "C42") (pin "2") (pinfunction "2_2") (pintype "passive"))
      (node (ref "U5") (pin "17") (pinfunction "CCFG_17") (pintype "bidirectional"))
      (node (ref "U5") (pin "2") (pinfunction "AVDD_2") (pintype "bidirectional"))
    )
    (net (code "131") (name "Net-(U5-AVSS)") (class "Default")
      (node (ref "BAT") (pin "5") (pinfunction "5_5") (pintype "passive"))
      (node (ref "C38") (pin "2") (pinfunction "2_2") (pintype "passive"))
      (node (ref "C39") (pin "2") (pinfunction "2_2") (pintype "passive"))
      (node (ref "C40") (pin "2") (pinfunction "2_2") (pintype "passive"))
      (node (ref "C41") (pin "2") (pinfunction "2_2") (pintype "passive"))
      (node (ref "C42") (pin "1") (pinfunction "1_1") (pintype "passive"))
      (node (ref "C43") (pin "2") (pinfunction "2_2") (pintype "passive"))
      (node (ref "C44") (pin "1") (pinfunction "1_1") (pintype "passive"))
      (node (ref "C46") (pin "2") (pinfunction "2_2") (pintype "passive"))
      (node (ref "R36") (pin "2") (pinfunction "2_2") (pintype "passive"))
      (node (ref "R37") (pin "2") (pinfunction "2_2") (pintype "passive"))
      (node (ref "R62") (pin "2") (pinfunction "2_2") (pintype "passive"))
      (node (ref "U5") (pin "18") (pinfunction "CTRC_18") (pintype "bidirectional"))
      (node (ref "U5") (pin "19") (pinfunction "CTRD_19") (pintype "bidirectional"))
      (node (ref "U5") (pin "20") (pinfunction "DVSS_20") (pintype "bidirectional"))
      (node (ref "U5") (pin "8") (pinfunction "AVSS_8") (pintype "bidirectional"))
    )
    (net (code "132") (name "Net-(U5-CHG)") (class "Default")
      (node (ref "R43") (pin "1") (pinfunction "1_1") (pintype "passive"))
      (node (ref "U5") (pin "13") (pinfunction "CHG_13") (pintype "bidirectional"))
    )
    (net (code "133") (name "Net-(U5-DSG)") (class "Default")
      (node (ref "R40") (pin "2") (pinfunction "2_2") (pintype "passive"))
      (node (ref "U5") (pin "11") (pinfunction "DSG_11") (pintype "bidirectional"))
    )
    (net (code "134") (name "Net-(U5-LD)") (class "Default")
      (node (ref "R44") (pin "1") (pinfunction "1_1") (pintype "passive"))
      (node (ref "U5") (pin "14") (pinfunction "LD_14") (pintype "bidirectional"))
    )
    (net (code "135") (name "Net-(U5-SRN)") (class "Default")
      (node (ref "C45") (pin "2") (pinfunction "2_2") (pintype "passive"))
      (node (ref "C46") (pin "1") (pinfunction "1_1") (pintype "passive"))
      (node (ref "R38") (pin "1") (pinfunction "1_1") (pintype "passive"))
      (node (ref "U5") (pin "10") (pinfunction "SRN_10") (pintype "bidirectional"))
    )
    (net (code "136") (name "Net-(U5-SRP)") (class "Default")
      (node (ref "C44") (pin "2") (pinfunction "2_2") (pintype "passive"))
      (node (ref "C45") (pin "1") (pinfunction "1_1") (pintype "passive"))
      (node (ref "R37") (pin "1") (pinfunction "1_1") (pintype "passive"))
      (node (ref "U5") (pin "9") (pinfunction "SRP_9") (pintype "bidirectional"))
    )
    (net (code "137") (name "Net-(U5-TS)") (class "Default")
      (node (ref "R35") (pin "2") (pinfunction "2_2") (pintype "passive"))
      (node (ref "R62") (pin "1") (pinfunction "1_1") (pintype "passive"))
      (node (ref "U5") (pin "15") (pinfunction "TS_15") (pintype "bidirectional"))
    )
    (net (code "138") (name "Net-(U5-VC1)") (class "Default")
      (node (ref "C39") (pin "1") (pinfunction "1_1") (pintype "passive"))
      (node (ref "R33") (pin "2") (pinfunction "2_2") (pintype "passive"))
      (node (ref "U5") (pin "7") (pinfunction "VC1_7") (pintype "bidirectional"))
    )
    (net (code "139") (name "Net-(U5-VC2)") (class "Default")
      (node (ref "C40") (pin "1") (pinfunction "1_1") (pintype "passive"))
      (node (ref "R32") (pin "2") (pinfunction "2_2") (pintype "passive"))
      (node (ref "U5") (pin "6") (pinfunction "VC2_6") (pintype "bidirectional"))
    )
    (net (code "140") (name "Net-(U5-VC3)") (class "Default")
      (node (ref "C41") (pin "1") (pinfunction "1_1") (pintype "passive"))
      (node (ref "R31") (pin "2") (pinfunction "2_2") (pintype "passive"))
      (node (ref "U5") (pin "5") (pinfunction "VC3_5") (pintype "bidirectional"))
    )
    (net (code "141") (name "Net-(U5-VC4)") (class "Default")
      (node (ref "C38") (pin "1") (pinfunction "1_1") (pintype "passive"))
      (node (ref "R30") (pin "2") (pinfunction "2_2") (pintype "passive"))
      (node (ref "U5") (pin "3") (pinfunction "VC5_3") (pintype "bidirectional"))
      (node (ref "U5") (pin "4") (pinfunction "VC4_4") (pintype "bidirectional"))
    )
    (net (code "142") (name "Net-(U5-VDD)") (class "Default")
      (node (ref "C43") (pin "1") (pinfunction "1_1") (pintype "passive"))
      (node (ref "R34") (pin "2") (pinfunction "2_2") (pintype "passive"))
      (node (ref "U5") (pin "1") (pinfunction "VDD_1") (pintype "bidirectional"))
    )
    (net (code "143") (name "Net-(U5-VTB)") (class "Default")
      (node (ref "R35") (pin "1") (pinfunction "1_1") (pintype "passive"))
      (node (ref "U5") (pin "16") (pinfunction "VTB_16") (pintype "bidirectional"))
    )
    (net (code "144") (name "unconnected-(D8-PadA)") (class "Default")
      (node (ref "D8") (pin "A") (pinfunction "A_A") (pintype "passive"))
    )
    (net (code "145") (name "unconnected-(D9-PadA)") (class "Default")
      (node (ref "D9") (pin "A") (pinfunction "A_A") (pintype "passive"))
    )
    (net (code "146") (name "unconnected-(IC1-SAFEBOOT_N-Pad8)") (class "Default")
      (node (ref "IC1") (pin "8") (pinfunction "SAFEBOOT_N_8") (pintype "bidirectional"))
    )
    (net (code "147") (name "unconnected-(IC1-TP-Pad7)") (class "Default")
      (node (ref "IC1") (pin "7") (pinfunction "TP_7") (pintype "bidirectional"))
    )
    (net (code "148") (name "unconnected-(IC2-BK_O-Pad10)") (class "Default")
      (node (ref "IC2") (pin "10") (pinfunction "BK_O_10") (pintype "bidirectional"))
    )
    (net (code "149") (name "unconnected-(IC2-NC-Pad20)") (class "Default")
      (node (ref "IC2") (pin "20") (pinfunction "NC_20") (pintype "no_connect"))
    )
    (net (code "150") (name "unconnected-(IC2-P0_0{slash}CTS-Pad15)") (class "Default")
      (node (ref "IC2") (pin "15") (pinfunction "P0_0/CTS_15") (pintype "bidirectional"))
    )
    (net (code "151") (name "unconnected-(IC2-P0_7-Pad29)") (class "Default")
      (node (ref "IC2") (pin "29") (pinfunction "P0_7_29") (pintype "bidirectional"))
    )
    (net (code "152") (name "unconnected-(IC2-P1_0-Pad16)") (class "Default")
      (node (ref "IC2") (pin "16") (pinfunction "P1_0_16") (pintype "bidirectional"))
    )
    (net (code "153") (name "unconnected-(IC2-P1_1-Pad12)") (class "Default")
      (node (ref "IC2") (pin "12") (pinfunction "P1_1_12") (pintype "bidirectional"))
    )
    (net (code "154") (name "unconnected-(IC2-P1_2{slash}SCL-Pad13)") (class "Default")
      (node (ref "IC2") (pin "13") (pinfunction "P1_2/SCL_13") (pintype "bidirectional"))
    )
    (net (code "155") (name "unconnected-(IC2-P1_3{slash}SDA-Pad14)") (class "Default")
      (node (ref "IC2") (pin "14") (pinfunction "P1_3/SDA_14") (pintype "bidirectional"))
    )
    (net (code "156") (name "unconnected-(IC2-P2_2-Pad5)") (class "Default")
      (node (ref "IC2") (pin "5") (pinfunction "P2_2_5") (pintype "bidirectional"))
    )
    (net (code "157") (name "unconnected-(IC2-P2_3-Pad9)") (class "Default")
      (node (ref "IC2") (pin "9") (pinfunction "P2_3_9") (pintype "bidirectional"))
    )
    (net (code "158") (name "unconnected-(IC2-P2_4-Pad19)") (class "Default")
      (node (ref "IC2") (pin "19") (pinfunction "P2_4_19") (pintype "bidirectional"))
    )
    (net (code "159") (name "unconnected-(IC2-P2_7{slash}TX_IND-Pad11)") (class "Default")
      (node (ref "IC2") (pin "11") (pinfunction "P2_7/TX_IND_11") (pintype "bidirectional"))
    )
    (net (code "160") (name "unconnected-(IC2-P3_1-Pad24)") (class "Default")
      (node (ref "IC2") (pin "24") (pinfunction "P3_1_24") (pintype "bidirectional"))
    )
    (net (code "161") (name "unconnected-(IC2-P3_2-Pad25)") (class "Default")
      (node (ref "IC2") (pin "25") (pinfunction "P3_2_25") (pintype "bidirectional"))
    )
    (net (code "162") (name "unconnected-(IC2-P3_3-Pad26)") (class "Default")
      (node (ref "IC2") (pin "26") (pinfunction "P3_3_26") (pintype "bidirectional"))
    )
    (net (code "163") (name "unconnected-(IC2-P3_4-Pad27)") (class "Default")
      (node (ref "IC2") (pin "27") (pinfunction "P3_4_27") (pintype "bidirectional"))
    )
    (net (code "164") (name "unconnected-(IC2-P3_5-Pad28)") (class "Default")
      (node (ref "IC2") (pin "28") (pinfunction "P3_5_28") (pintype "bidirectional"))
    )
    (net (code "165") (name "unconnected-(IC2-P3_6{slash}RTS-Pad17)") (class "Default")
      (node (ref "IC2") (pin "17") (pinfunction "P3_6/RTS_17") (pintype "bidirectional"))
    )
    (net (code "166") (name "unconnected-(IC2-ULC_O-Pad8)") (class "Default")
      (node (ref "IC2") (pin "8") (pinfunction "ULC_O_8") (pintype "bidirectional"))
    )
    (net (code "167") (name "unconnected-(IC2-VDD_IO(1)-Pad6)") (class "Default")
      (node (ref "IC2") (pin "6") (pinfunction "VDD_IO(1)_6") (pintype "bidirectional"))
    )
    (net (code "168") (name "unconnected-(IC2-VDD_IO(2)-Pad7)") (class "Default")
      (node (ref "IC2") (pin "7") (pinfunction "VDD_IO(2)_7") (pintype "bidirectional"))
    )
    (net (code "169") (name "unconnected-(J1-PadID)") (class "Default")
      (node (ref "J1") (pin "ID") (pinfunction "ID_ID") (pintype "bidirectional"))
    )
    (net (code "170") (name "unconnected-(U$1-NC1-Pad5)") (class "Default")
      (node (ref "U$1") (pin "5") (pinfunction "NC1_5") (pintype "no_connect"))
    )
    (net (code "171") (name "unconnected-(U$1-NC2-Pad6)") (class "Default")
      (node (ref "U$1") (pin "6") (pinfunction "NC2_6") (pintype "no_connect"))
    )
    (net (code "172") (name "unconnected-(U$1-NC3-Pad11)") (class "Default")
      (node (ref "U$1") (pin "11") (pinfunction "NC3_11") (pintype "no_connect"))
    )
    (net (code "173") (name "unconnected-(U$1-NC4-Pad13)") (class "Default")
      (node (ref "U$1") (pin "13") (pinfunction "NC4_13") (pintype "no_connect"))
    )
    (net (code "174") (name "unconnected-(U$1-NC5-Pad16)") (class "Default")
      (node (ref "U$1") (pin "16") (pinfunction "NC5_16") (pintype "no_connect"))
    )
    (net (code "175") (name "unconnected-(U$1-NC6-Pad18)") (class "Default")
      (node (ref "U$1") (pin "18") (pinfunction "NC6_18") (pintype "no_connect"))
    )
    (net (code "176") (name "unconnected-(U2-PB3-Pad55)") (class "Default")
      (node (ref "U2") (pin "55") (pinfunction "PB3_55") (pintype "bidirectional"))
    )
    (net (code "177") (name "unconnected-(U2-PB4-Pad56)") (class "Default")
      (node (ref "U2") (pin "56") (pinfunction "PB4_56") (pintype "bidirectional"))
    )
    (net (code "178") (name "unconnected-(U2-PB5-Pad57)") (class "Default")
      (node (ref "U2") (pin "57") (pinfunction "PB5_57") (pintype "bidirectional"))
    )
    (net (code "179") (name "unconnected-(U2-PB6-Pad58)") (class "Default")
      (node (ref "U2") (pin "58") (pinfunction "PB6_58") (pintype "bidirectional"))
    )
    (net (code "180") (name "unconnected-(U2-PB7-Pad59)") (class "Default")
      (node (ref "U2") (pin "59") (pinfunction "PB7_59") (pintype "bidirectional"))
    )
    (net (code "181") (name "unconnected-(U2-PB8-Pad61)") (class "Default")
      (node (ref "U2") (pin "61") (pinfunction "PB8_61") (pintype "bidirectional"))
    )
    (net (code "182") (name "unconnected-(U2-PB9-Pad62)") (class "Default")
      (node (ref "U2") (pin "62") (pinfunction "PB9_62") (pintype "bidirectional"))
    )
    (net (code "183") (name "unconnected-(U2-PC13-Pad2)") (class "Default")
      (node (ref "U2") (pin "2") (pinfunction "PC13_2") (pintype "bidirectional"))
    )
    (net (code "184") (name "unconnected-(U2-PC14-OSC32_IN-Pad3)") (class "Default")
      (node (ref "U2") (pin "3") (pinfunction "PC14-OSC32_IN_3") (pintype "bidirectional"))
    )
    (net (code "185") (name "unconnected-(U2-PC15-OSC32_OUT-Pad4)") (class "Default")
      (node (ref "U2") (pin "4") (pinfunction "PC15-OSC32_OUT_4") (pintype "bidirectional"))
    )
    (net (code "186") (name "unconnected-(U3-GP0{slash}SSPND-Pad16)") (class "Default")
      (node (ref "U3") (pin "16") (pinfunction "GP0/SSPND_16") (pintype "bidirectional"))
    )
    (net (code "187") (name "unconnected-(U3-GP1{slash}USBCFG-Pad15)") (class "Default")
      (node (ref "U3") (pin "15") (pinfunction "GP1/USBCFG_15") (pintype "bidirectional"))
    )
    (net (code "188") (name "unconnected-(U3-GP2-Pad14)") (class "Default")
      (node (ref "U3") (pin "14") (pinfunction "GP2_14") (pintype "bidirectional"))
    )
    (net (code "189") (name "unconnected-(U3-GP3-Pad9)") (class "Default")
      (node (ref "U3") (pin "9") (pinfunction "GP3_9") (pintype "bidirectional"))
    )
    (net (code "190") (name "unconnected-(U3-GP4-Pad8)") (class "Default")
      (node (ref "U3") (pin "8") (pinfunction "GP4_8") (pintype "bidirectional"))
    )
    (net (code "191") (name "unconnected-(U3-GP5-Pad7)") (class "Default")
      (node (ref "U3") (pin "7") (pinfunction "GP5_7") (pintype "bidirectional"))
    )
    (net (code "192") (name "unconnected-(U3-N_CTS-Pad13)") (class "Default")
      (node (ref "U3") (pin "13") (pinfunction "N_CTS_13") (pintype "input"))
    )
    (net (code "193") (name "unconnected-(U3-N_RTS-Pad11)") (class "Default")
      (node (ref "U3") (pin "11") (pinfunction "N_RTS_11") (pintype "output"))
    )
    (net (code "194") (name "unconnected-(U5-CHGU-Pad12)") (class "Default")
      (node (ref "U5") (pin "12") (pinfunction "CHGU_12") (pintype "bidirectional"))
    )
  )
)
